# LED_Array_Large.net
KiCad netlist of a schematic drawn in Altium Designer
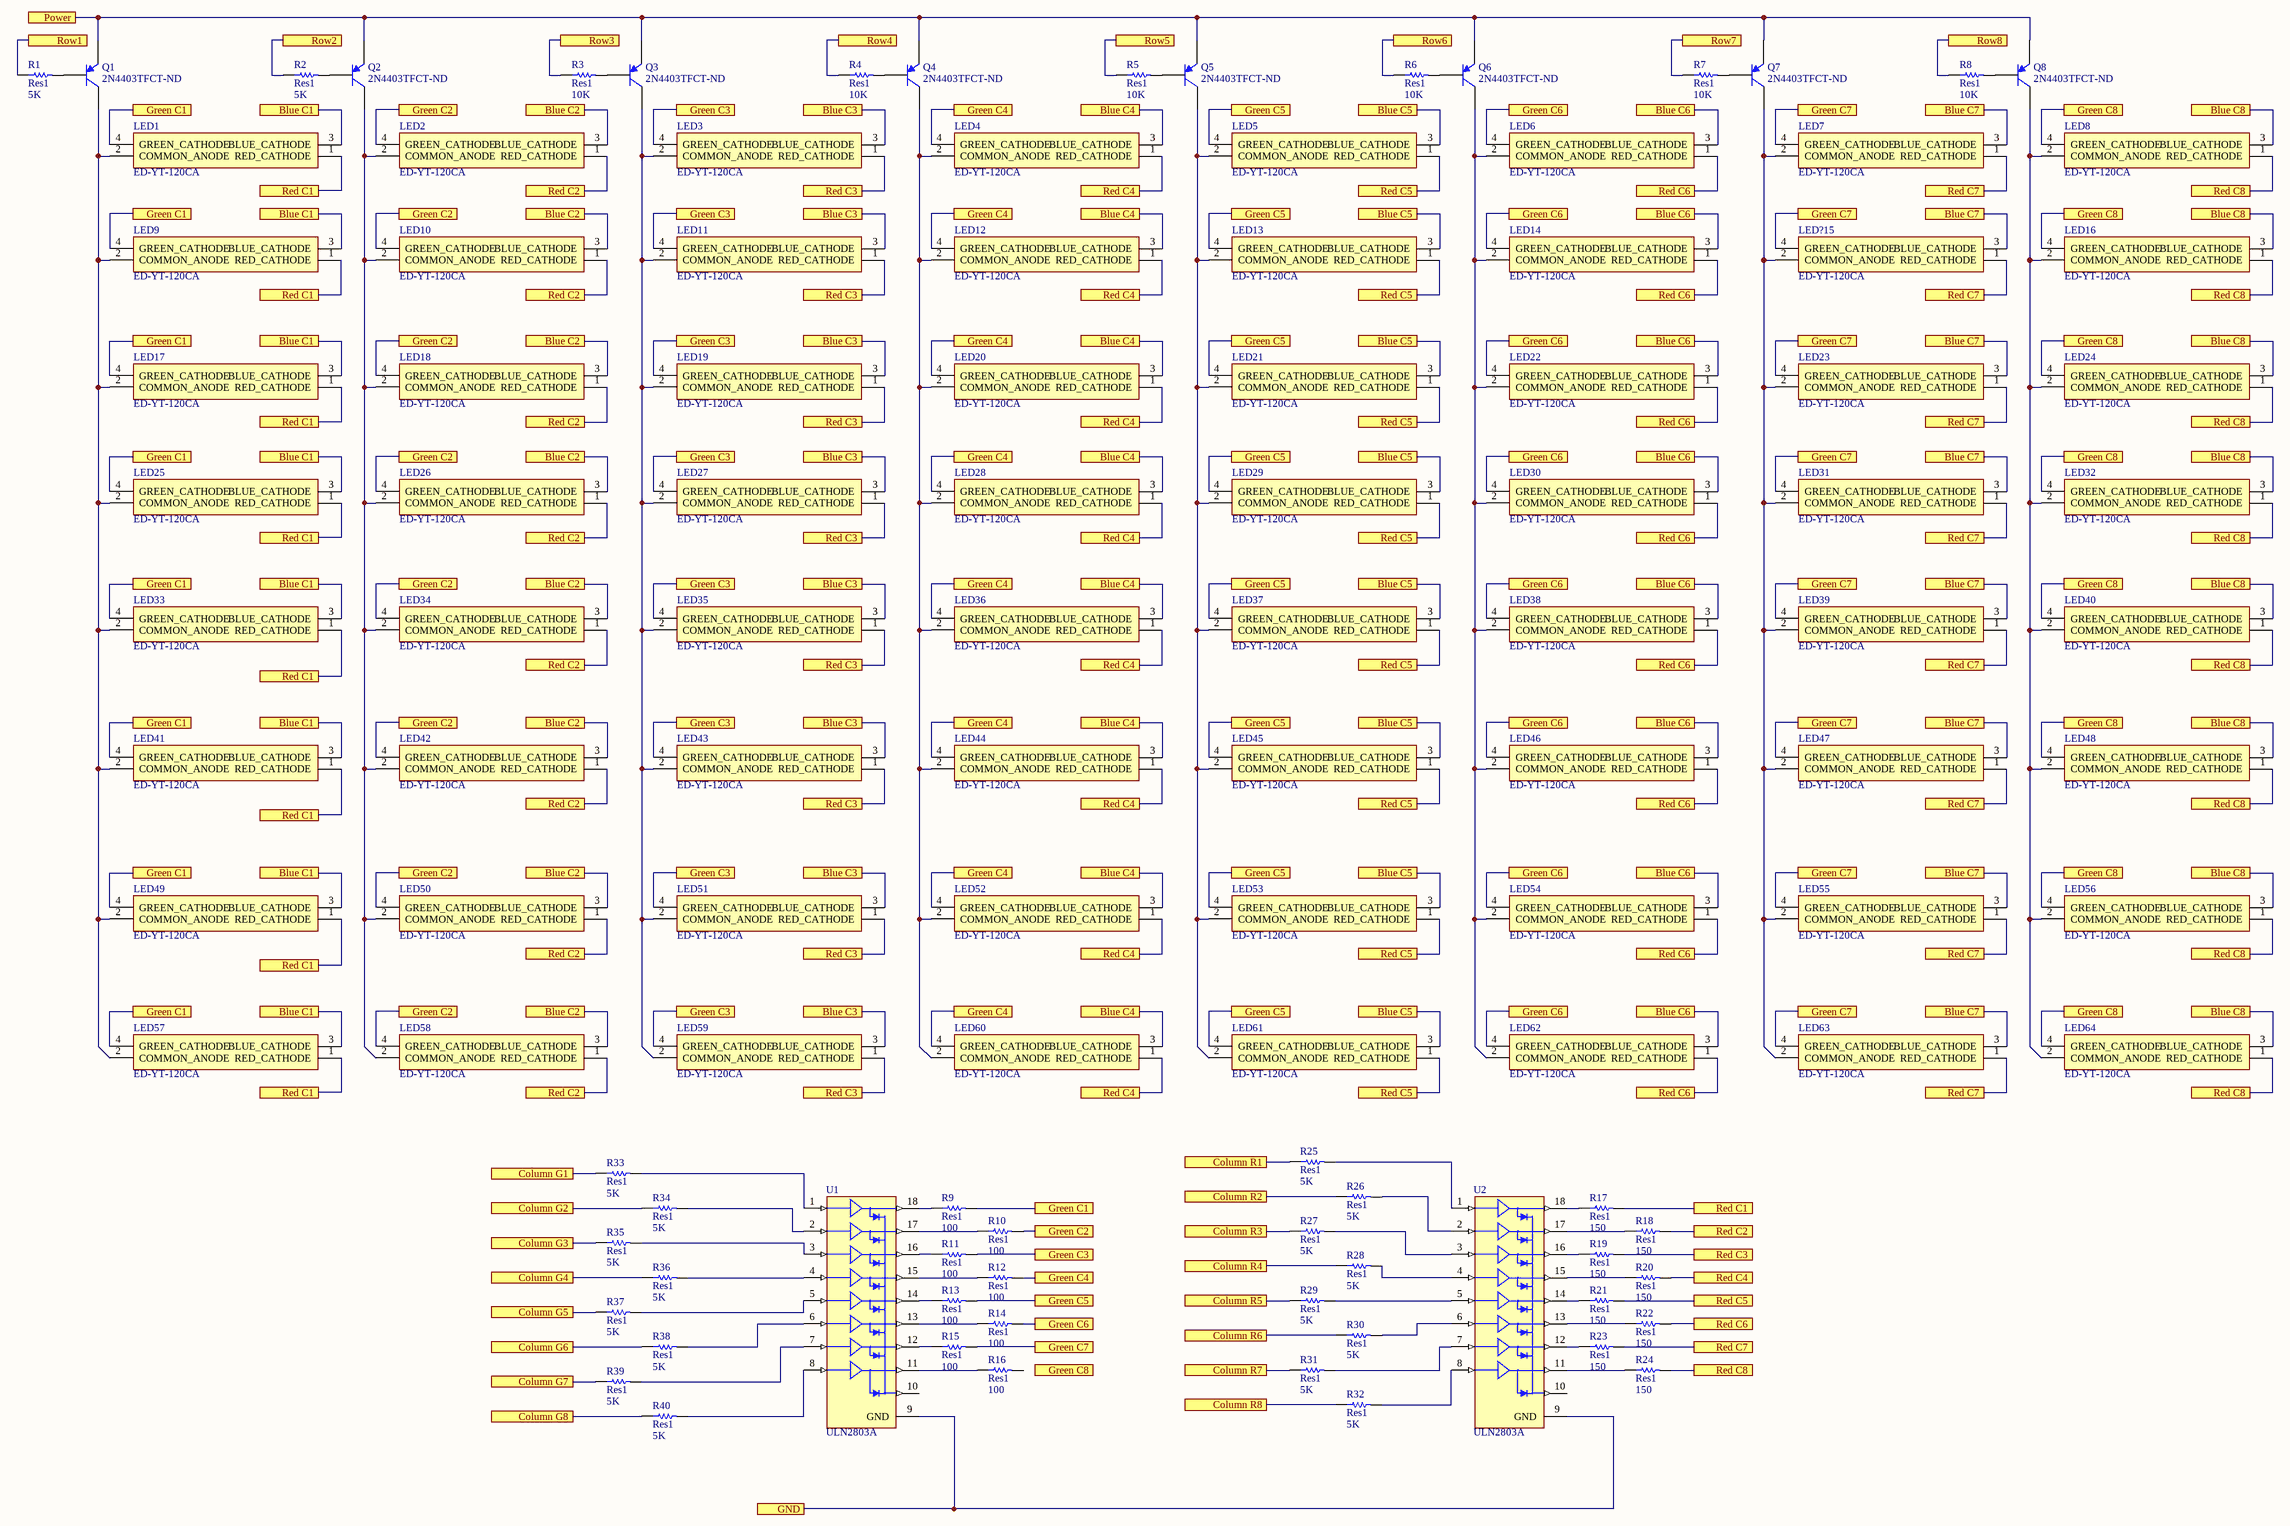
[diagram p0: LED_Array_Large.SchDoc]

(export (version "E")
  (design (tool "Eeschema 10.0.6"))
  (components
    (comp (ref "LED1")
      (value "ED-YT-120CA")
      (footprint "SamacSys:L-154A4SUREQBFZGEC")
      (description "LED")
      (fields
        (field (name "MANUFACTURER_PART_NUMBER") "WP154A4SEJ3VBDZGW/CA")
        (field (name "MOUSER PART NUMBER") "604-WP154A43VBDZGWCA")
      )
      (libsource (lib "SamacSys") (part "WP154A4SEJ3VBDZGW_CA"))
    )
    (comp (ref "LED2")
      (value "ED-YT-120CA")
      (footprint "SamacSys:L-154A4SUREQBFZGEC")
      (description "LED")
      (fields
        (field (name "MANUFACTURER_PART_NUMBER") "WP154A4SEJ3VBDZGW/CA")
        (field (name "MOUSER PART NUMBER") "604-WP154A43VBDZGWCA")
      )
      (libsource (lib "*") (part "WP154A4SEJ3VBDZGW_CA"))
    )
    (comp (ref "LED3")
      (value "ED-YT-120CA")
      (footprint "SamacSys:L-154A4SUREQBFZGEC")
      (description "LED")
      (fields
        (field (name "MANUFACTURER_PART_NUMBER") "WP154A4SEJ3VBDZGW/CA")
        (field (name "MOUSER PART NUMBER") "604-WP154A43VBDZGWCA")
      )
      (libsource (lib "SamacSys") (part "WP154A4SEJ3VBDZGW_CA"))
    )
    (comp (ref "LED4")
      (value "ED-YT-120CA")
      (footprint "SamacSys:L-154A4SUREQBFZGEC")
      (description "LED")
      (fields
        (field (name "MANUFACTURER_PART_NUMBER") "WP154A4SEJ3VBDZGW/CA")
        (field (name "MOUSER PART NUMBER") "604-WP154A43VBDZGWCA")
      )
      (libsource (lib "*") (part "WP154A4SEJ3VBDZGW_CA"))
    )
    (comp (ref "LED5")
      (value "ED-YT-120CA")
      (footprint "SamacSys:L-154A4SUREQBFZGEC")
      (description "LED")
      (fields
        (field (name "MANUFACTURER_PART_NUMBER") "WP154A4SEJ3VBDZGW/CA")
        (field (name "MOUSER PART NUMBER") "604-WP154A43VBDZGWCA")
      )
      (libsource (lib "SamacSys") (part "WP154A4SEJ3VBDZGW_CA"))
    )
    (comp (ref "LED6")
      (value "ED-YT-120CA")
      (footprint "SamacSys:L-154A4SUREQBFZGEC")
      (description "LED")
      (fields
        (field (name "MANUFACTURER_PART_NUMBER") "WP154A4SEJ3VBDZGW/CA")
        (field (name "MOUSER PART NUMBER") "604-WP154A43VBDZGWCA")
      )
      (libsource (lib "*") (part "WP154A4SEJ3VBDZGW_CA"))
    )
    (comp (ref "LED7")
      (value "ED-YT-120CA")
      (footprint "SamacSys:L-154A4SUREQBFZGEC")
      (description "LED")
      (fields
        (field (name "MANUFACTURER_PART_NUMBER") "WP154A4SEJ3VBDZGW/CA")
        (field (name "MOUSER PART NUMBER") "604-WP154A43VBDZGWCA")
      )
      (libsource (lib "SamacSys") (part "WP154A4SEJ3VBDZGW_CA"))
    )
    (comp (ref "LED8")
      (value "ED-YT-120CA")
      (footprint "SamacSys:L-154A4SUREQBFZGEC")
      (description "LED")
      (fields
        (field (name "MANUFACTURER_PART_NUMBER") "WP154A4SEJ3VBDZGW/CA")
        (field (name "MOUSER PART NUMBER") "604-WP154A43VBDZGWCA")
      )
      (libsource (lib "*") (part "WP154A4SEJ3VBDZGW_CA"))
    )
    (comp (ref "LED9")
      (value "ED-YT-120CA")
      (footprint "SamacSys:L-154A4SUREQBFZGEC")
      (description "LED")
      (fields
        (field (name "MANUFACTURER_PART_NUMBER") "WP154A4SEJ3VBDZGW/CA")
        (field (name "MOUSER PART NUMBER") "604-WP154A43VBDZGWCA")
      )
      (libsource (lib "SamacSys") (part "WP154A4SEJ3VBDZGW_CA"))
    )
    (comp (ref "LED10")
      (value "ED-YT-120CA")
      (footprint "SamacSys:L-154A4SUREQBFZGEC")
      (description "LED")
      (fields
        (field (name "MANUFACTURER_PART_NUMBER") "WP154A4SEJ3VBDZGW/CA")
        (field (name "MOUSER PART NUMBER") "604-WP154A43VBDZGWCA")
      )
      (libsource (lib "*") (part "WP154A4SEJ3VBDZGW_CA"))
    )
    (comp (ref "LED11")
      (value "ED-YT-120CA")
      (footprint "SamacSys:L-154A4SUREQBFZGEC")
      (description "LED")
      (fields
        (field (name "MANUFACTURER_PART_NUMBER") "WP154A4SEJ3VBDZGW/CA")
        (field (name "MOUSER PART NUMBER") "604-WP154A43VBDZGWCA")
      )
      (libsource (lib "SamacSys") (part "WP154A4SEJ3VBDZGW_CA"))
    )
    (comp (ref "LED12")
      (value "ED-YT-120CA")
      (footprint "SamacSys:L-154A4SUREQBFZGEC")
      (description "LED")
      (fields
        (field (name "MANUFACTURER_PART_NUMBER") "WP154A4SEJ3VBDZGW/CA")
        (field (name "MOUSER PART NUMBER") "604-WP154A43VBDZGWCA")
      )
      (libsource (lib "*") (part "WP154A4SEJ3VBDZGW_CA"))
    )
    (comp (ref "LED13")
      (value "ED-YT-120CA")
      (footprint "SamacSys:L-154A4SUREQBFZGEC")
      (description "LED")
      (fields
        (field (name "MANUFACTURER_PART_NUMBER") "WP154A4SEJ3VBDZGW/CA")
        (field (name "MOUSER PART NUMBER") "604-WP154A43VBDZGWCA")
      )
      (libsource (lib "SamacSys") (part "WP154A4SEJ3VBDZGW_CA"))
    )
    (comp (ref "LED14")
      (value "ED-YT-120CA")
      (footprint "SamacSys:L-154A4SUREQBFZGEC")
      (description "LED")
      (fields
        (field (name "MANUFACTURER_PART_NUMBER") "WP154A4SEJ3VBDZGW/CA")
        (field (name "MOUSER PART NUMBER") "604-WP154A43VBDZGWCA")
      )
      (libsource (lib "*") (part "WP154A4SEJ3VBDZGW_CA"))
    )
    (comp (ref "LED16")
      (value "ED-YT-120CA")
      (footprint "SamacSys:L-154A4SUREQBFZGEC")
      (description "LED")
      (fields
        (field (name "MANUFACTURER_PART_NUMBER") "WP154A4SEJ3VBDZGW/CA")
        (field (name "MOUSER PART NUMBER") "604-WP154A43VBDZGWCA")
      )
      (libsource (lib "*") (part "WP154A4SEJ3VBDZGW_CA"))
    )
    (comp (ref "LED17")
      (value "ED-YT-120CA")
      (footprint "SamacSys:L-154A4SUREQBFZGEC")
      (description "LED")
      (fields
        (field (name "MANUFACTURER_PART_NUMBER") "WP154A4SEJ3VBDZGW/CA")
        (field (name "MOUSER PART NUMBER") "604-WP154A43VBDZGWCA")
      )
      (libsource (lib "SamacSys") (part "WP154A4SEJ3VBDZGW_CA"))
    )
    (comp (ref "LED18")
      (value "ED-YT-120CA")
      (footprint "SamacSys:L-154A4SUREQBFZGEC")
      (description "LED")
      (fields
        (field (name "MANUFACTURER_PART_NUMBER") "WP154A4SEJ3VBDZGW/CA")
        (field (name "MOUSER PART NUMBER") "604-WP154A43VBDZGWCA")
      )
      (libsource (lib "*") (part "WP154A4SEJ3VBDZGW_CA"))
    )
    (comp (ref "LED19")
      (value "ED-YT-120CA")
      (footprint "SamacSys:L-154A4SUREQBFZGEC")
      (description "LED")
      (fields
        (field (name "MANUFACTURER_PART_NUMBER") "WP154A4SEJ3VBDZGW/CA")
        (field (name "MOUSER PART NUMBER") "604-WP154A43VBDZGWCA")
      )
      (libsource (lib "SamacSys") (part "WP154A4SEJ3VBDZGW_CA"))
    )
    (comp (ref "LED20")
      (value "ED-YT-120CA")
      (footprint "SamacSys:L-154A4SUREQBFZGEC")
      (description "LED")
      (fields
        (field (name "MANUFACTURER_PART_NUMBER") "WP154A4SEJ3VBDZGW/CA")
        (field (name "MOUSER PART NUMBER") "604-WP154A43VBDZGWCA")
      )
      (libsource (lib "*") (part "WP154A4SEJ3VBDZGW_CA"))
    )
    (comp (ref "LED21")
      (value "ED-YT-120CA")
      (footprint "SamacSys:L-154A4SUREQBFZGEC")
      (description "LED")
      (fields
        (field (name "MANUFACTURER_PART_NUMBER") "WP154A4SEJ3VBDZGW/CA")
        (field (name "MOUSER PART NUMBER") "604-WP154A43VBDZGWCA")
      )
      (libsource (lib "SamacSys") (part "WP154A4SEJ3VBDZGW_CA"))
    )
    (comp (ref "LED22")
      (value "ED-YT-120CA")
      (footprint "SamacSys:L-154A4SUREQBFZGEC")
      (description "LED")
      (fields
        (field (name "MANUFACTURER_PART_NUMBER") "WP154A4SEJ3VBDZGW/CA")
        (field (name "MOUSER PART NUMBER") "604-WP154A43VBDZGWCA")
      )
      (libsource (lib "*") (part "WP154A4SEJ3VBDZGW_CA"))
    )
    (comp (ref "LED23")
      (value "ED-YT-120CA")
      (footprint "SamacSys:L-154A4SUREQBFZGEC")
      (description "LED")
      (fields
        (field (name "MANUFACTURER_PART_NUMBER") "WP154A4SEJ3VBDZGW/CA")
        (field (name "MOUSER PART NUMBER") "604-WP154A43VBDZGWCA")
      )
      (libsource (lib "SamacSys") (part "WP154A4SEJ3VBDZGW_CA"))
    )
    (comp (ref "LED24")
      (value "ED-YT-120CA")
      (footprint "SamacSys:L-154A4SUREQBFZGEC")
      (description "LED")
      (fields
        (field (name "MANUFACTURER_PART_NUMBER") "WP154A4SEJ3VBDZGW/CA")
        (field (name "MOUSER PART NUMBER") "604-WP154A43VBDZGWCA")
      )
      (libsource (lib "*") (part "WP154A4SEJ3VBDZGW_CA"))
    )
    (comp (ref "LED25")
      (value "ED-YT-120CA")
      (footprint "SamacSys:L-154A4SUREQBFZGEC")
      (description "LED")
      (fields
        (field (name "MANUFACTURER_PART_NUMBER") "WP154A4SEJ3VBDZGW/CA")
        (field (name "MOUSER PART NUMBER") "604-WP154A43VBDZGWCA")
      )
      (libsource (lib "SamacSys") (part "WP154A4SEJ3VBDZGW_CA"))
    )
    (comp (ref "LED26")
      (value "ED-YT-120CA")
      (footprint "SamacSys:L-154A4SUREQBFZGEC")
      (description "LED")
      (fields
        (field (name "MANUFACTURER_PART_NUMBER") "WP154A4SEJ3VBDZGW/CA")
        (field (name "MOUSER PART NUMBER") "604-WP154A43VBDZGWCA")
      )
      (libsource (lib "*") (part "WP154A4SEJ3VBDZGW_CA"))
    )
    (comp (ref "LED27")
      (value "ED-YT-120CA")
      (footprint "SamacSys:L-154A4SUREQBFZGEC")
      (description "LED")
      (fields
        (field (name "MANUFACTURER_PART_NUMBER") "WP154A4SEJ3VBDZGW/CA")
        (field (name "MOUSER PART NUMBER") "604-WP154A43VBDZGWCA")
      )
      (libsource (lib "SamacSys") (part "WP154A4SEJ3VBDZGW_CA"))
    )
    (comp (ref "LED28")
      (value "ED-YT-120CA")
      (footprint "SamacSys:L-154A4SUREQBFZGEC")
      (description "LED")
      (fields
        (field (name "MANUFACTURER_PART_NUMBER") "WP154A4SEJ3VBDZGW/CA")
        (field (name "MOUSER PART NUMBER") "604-WP154A43VBDZGWCA")
      )
      (libsource (lib "*") (part "WP154A4SEJ3VBDZGW_CA"))
    )
    (comp (ref "LED29")
      (value "ED-YT-120CA")
      (footprint "SamacSys:L-154A4SUREQBFZGEC")
      (description "LED")
      (fields
        (field (name "MANUFACTURER_PART_NUMBER") "WP154A4SEJ3VBDZGW/CA")
        (field (name "MOUSER PART NUMBER") "604-WP154A43VBDZGWCA")
      )
      (libsource (lib "SamacSys") (part "WP154A4SEJ3VBDZGW_CA"))
    )
    (comp (ref "LED30")
      (value "ED-YT-120CA")
      (footprint "SamacSys:L-154A4SUREQBFZGEC")
      (description "LED")
      (fields
        (field (name "MANUFACTURER_PART_NUMBER") "WP154A4SEJ3VBDZGW/CA")
        (field (name "MOUSER PART NUMBER") "604-WP154A43VBDZGWCA")
      )
      (libsource (lib "*") (part "WP154A4SEJ3VBDZGW_CA"))
    )
    (comp (ref "LED31")
      (value "ED-YT-120CA")
      (footprint "SamacSys:L-154A4SUREQBFZGEC")
      (description "LED")
      (fields
        (field (name "MANUFACTURER_PART_NUMBER") "WP154A4SEJ3VBDZGW/CA")
        (field (name "MOUSER PART NUMBER") "604-WP154A43VBDZGWCA")
      )
      (libsource (lib "SamacSys") (part "WP154A4SEJ3VBDZGW_CA"))
    )
    (comp (ref "LED32")
      (value "ED-YT-120CA")
      (footprint "SamacSys:L-154A4SUREQBFZGEC")
      (description "LED")
      (fields
        (field (name "MANUFACTURER_PART_NUMBER") "WP154A4SEJ3VBDZGW/CA")
        (field (name "MOUSER PART NUMBER") "604-WP154A43VBDZGWCA")
      )
      (libsource (lib "*") (part "WP154A4SEJ3VBDZGW_CA"))
    )
    (comp (ref "LED33")
      (value "ED-YT-120CA")
      (footprint "SamacSys:L-154A4SUREQBFZGEC")
      (description "LED")
      (fields
        (field (name "MANUFACTURER_PART_NUMBER") "WP154A4SEJ3VBDZGW/CA")
        (field (name "MOUSER PART NUMBER") "604-WP154A43VBDZGWCA")
      )
      (libsource (lib "SamacSys") (part "WP154A4SEJ3VBDZGW_CA"))
    )
    (comp (ref "LED34")
      (value "ED-YT-120CA")
      (footprint "SamacSys:L-154A4SUREQBFZGEC")
      (description "LED")
      (fields
        (field (name "MANUFACTURER_PART_NUMBER") "WP154A4SEJ3VBDZGW/CA")
        (field (name "MOUSER PART NUMBER") "604-WP154A43VBDZGWCA")
      )
      (libsource (lib "*") (part "WP154A4SEJ3VBDZGW_CA"))
    )
    (comp (ref "LED35")
      (value "ED-YT-120CA")
      (footprint "SamacSys:L-154A4SUREQBFZGEC")
      (description "LED")
      (fields
        (field (name "MANUFACTURER_PART_NUMBER") "WP154A4SEJ3VBDZGW/CA")
        (field (name "MOUSER PART NUMBER") "604-WP154A43VBDZGWCA")
      )
      (libsource (lib "SamacSys") (part "WP154A4SEJ3VBDZGW_CA"))
    )
    (comp (ref "LED36")
      (value "ED-YT-120CA")
      (footprint "SamacSys:L-154A4SUREQBFZGEC")
      (description "LED")
      (fields
        (field (name "MANUFACTURER_PART_NUMBER") "WP154A4SEJ3VBDZGW/CA")
        (field (name "MOUSER PART NUMBER") "604-WP154A43VBDZGWCA")
      )
      (libsource (lib "*") (part "WP154A4SEJ3VBDZGW_CA"))
    )
    (comp (ref "LED37")
      (value "ED-YT-120CA")
      (footprint "SamacSys:L-154A4SUREQBFZGEC")
      (description "LED")
      (fields
        (field (name "MANUFACTURER_PART_NUMBER") "WP154A4SEJ3VBDZGW/CA")
        (field (name "MOUSER PART NUMBER") "604-WP154A43VBDZGWCA")
      )
      (libsource (lib "SamacSys") (part "WP154A4SEJ3VBDZGW_CA"))
    )
    (comp (ref "LED38")
      (value "ED-YT-120CA")
      (footprint "SamacSys:L-154A4SUREQBFZGEC")
      (description "LED")
      (fields
        (field (name "MANUFACTURER_PART_NUMBER") "WP154A4SEJ3VBDZGW/CA")
        (field (name "MOUSER PART NUMBER") "604-WP154A43VBDZGWCA")
      )
      (libsource (lib "*") (part "WP154A4SEJ3VBDZGW_CA"))
    )
    (comp (ref "LED39")
      (value "ED-YT-120CA")
      (footprint "SamacSys:L-154A4SUREQBFZGEC")
      (description "LED")
      (fields
        (field (name "MANUFACTURER_PART_NUMBER") "WP154A4SEJ3VBDZGW/CA")
        (field (name "MOUSER PART NUMBER") "604-WP154A43VBDZGWCA")
      )
      (libsource (lib "SamacSys") (part "WP154A4SEJ3VBDZGW_CA"))
    )
    (comp (ref "LED40")
      (value "ED-YT-120CA")
      (footprint "SamacSys:L-154A4SUREQBFZGEC")
      (description "LED")
      (fields
        (field (name "MANUFACTURER_PART_NUMBER") "WP154A4SEJ3VBDZGW/CA")
        (field (name "MOUSER PART NUMBER") "604-WP154A43VBDZGWCA")
      )
      (libsource (lib "*") (part "WP154A4SEJ3VBDZGW_CA"))
    )
    (comp (ref "LED41")
      (value "ED-YT-120CA")
      (footprint "SamacSys:L-154A4SUREQBFZGEC")
      (description "LED")
      (fields
        (field (name "MANUFACTURER_PART_NUMBER") "WP154A4SEJ3VBDZGW/CA")
        (field (name "MOUSER PART NUMBER") "604-WP154A43VBDZGWCA")
      )
      (libsource (lib "SamacSys") (part "WP154A4SEJ3VBDZGW_CA"))
    )
    (comp (ref "LED42")
      (value "ED-YT-120CA")
      (footprint "SamacSys:L-154A4SUREQBFZGEC")
      (description "LED")
      (fields
        (field (name "MANUFACTURER_PART_NUMBER") "WP154A4SEJ3VBDZGW/CA")
        (field (name "MOUSER PART NUMBER") "604-WP154A43VBDZGWCA")
      )
      (libsource (lib "*") (part "WP154A4SEJ3VBDZGW_CA"))
    )
    (comp (ref "LED43")
      (value "ED-YT-120CA")
      (footprint "SamacSys:L-154A4SUREQBFZGEC")
      (description "LED")
      (fields
        (field (name "MANUFACTURER_PART_NUMBER") "WP154A4SEJ3VBDZGW/CA")
        (field (name "MOUSER PART NUMBER") "604-WP154A43VBDZGWCA")
      )
      (libsource (lib "SamacSys") (part "WP154A4SEJ3VBDZGW_CA"))
    )
    (comp (ref "LED44")
      (value "ED-YT-120CA")
      (footprint "SamacSys:L-154A4SUREQBFZGEC")
      (description "LED")
      (fields
        (field (name "MANUFACTURER_PART_NUMBER") "WP154A4SEJ3VBDZGW/CA")
        (field (name "MOUSER PART NUMBER") "604-WP154A43VBDZGWCA")
      )
      (libsource (lib "*") (part "WP154A4SEJ3VBDZGW_CA"))
    )
    (comp (ref "LED45")
      (value "ED-YT-120CA")
      (footprint "SamacSys:L-154A4SUREQBFZGEC")
      (description "LED")
      (fields
        (field (name "MANUFACTURER_PART_NUMBER") "WP154A4SEJ3VBDZGW/CA")
        (field (name "MOUSER PART NUMBER") "604-WP154A43VBDZGWCA")
      )
      (libsource (lib "SamacSys") (part "WP154A4SEJ3VBDZGW_CA"))
    )
    (comp (ref "LED46")
      (value "ED-YT-120CA")
      (footprint "SamacSys:L-154A4SUREQBFZGEC")
      (description "LED")
      (fields
        (field (name "MANUFACTURER_PART_NUMBER") "WP154A4SEJ3VBDZGW/CA")
        (field (name "MOUSER PART NUMBER") "604-WP154A43VBDZGWCA")
      )
      (libsource (lib "*") (part "WP154A4SEJ3VBDZGW_CA"))
    )
    (comp (ref "LED47")
      (value "ED-YT-120CA")
      (footprint "SamacSys:L-154A4SUREQBFZGEC")
      (description "LED")
      (fields
        (field (name "MANUFACTURER_PART_NUMBER") "WP154A4SEJ3VBDZGW/CA")
        (field (name "MOUSER PART NUMBER") "604-WP154A43VBDZGWCA")
      )
      (libsource (lib "SamacSys") (part "WP154A4SEJ3VBDZGW_CA"))
    )
    (comp (ref "LED48")
      (value "ED-YT-120CA")
      (footprint "SamacSys:L-154A4SUREQBFZGEC")
      (description "LED")
      (fields
        (field (name "MANUFACTURER_PART_NUMBER") "WP154A4SEJ3VBDZGW/CA")
        (field (name "MOUSER PART NUMBER") "604-WP154A43VBDZGWCA")
      )
      (libsource (lib "*") (part "WP154A4SEJ3VBDZGW_CA"))
    )
    (comp (ref "LED49")
      (value "ED-YT-120CA")
      (footprint "SamacSys:L-154A4SUREQBFZGEC")
      (description "LED")
      (fields
        (field (name "MANUFACTURER_PART_NUMBER") "WP154A4SEJ3VBDZGW/CA")
        (field (name "MOUSER PART NUMBER") "604-WP154A43VBDZGWCA")
      )
      (libsource (lib "SamacSys") (part "WP154A4SEJ3VBDZGW_CA"))
    )
    (comp (ref "LED50")
      (value "ED-YT-120CA")
      (footprint "SamacSys:L-154A4SUREQBFZGEC")
      (description "LED")
      (fields
        (field (name "MANUFACTURER_PART_NUMBER") "WP154A4SEJ3VBDZGW/CA")
        (field (name "MOUSER PART NUMBER") "604-WP154A43VBDZGWCA")
      )
      (libsource (lib "*") (part "WP154A4SEJ3VBDZGW_CA"))
    )
    (comp (ref "LED51")
      (value "ED-YT-120CA")
      (footprint "SamacSys:L-154A4SUREQBFZGEC")
      (description "LED")
      (fields
        (field (name "MANUFACTURER_PART_NUMBER") "WP154A4SEJ3VBDZGW/CA")
        (field (name "MOUSER PART NUMBER") "604-WP154A43VBDZGWCA")
      )
      (libsource (lib "SamacSys") (part "WP154A4SEJ3VBDZGW_CA"))
    )
    (comp (ref "LED52")
      (value "ED-YT-120CA")
      (footprint "SamacSys:L-154A4SUREQBFZGEC")
      (description "LED")
      (fields
        (field (name "MANUFACTURER_PART_NUMBER") "WP154A4SEJ3VBDZGW/CA")
        (field (name "MOUSER PART NUMBER") "604-WP154A43VBDZGWCA")
      )
      (libsource (lib "*") (part "WP154A4SEJ3VBDZGW_CA"))
    )
    (comp (ref "LED53")
      (value "ED-YT-120CA")
      (footprint "SamacSys:L-154A4SUREQBFZGEC")
      (description "LED")
      (fields
        (field (name "MANUFACTURER_PART_NUMBER") "WP154A4SEJ3VBDZGW/CA")
        (field (name "MOUSER PART NUMBER") "604-WP154A43VBDZGWCA")
      )
      (libsource (lib "SamacSys") (part "WP154A4SEJ3VBDZGW_CA"))
    )
    (comp (ref "LED54")
      (value "ED-YT-120CA")
      (footprint "SamacSys:L-154A4SUREQBFZGEC")
      (description "LED")
      (fields
        (field (name "MANUFACTURER_PART_NUMBER") "WP154A4SEJ3VBDZGW/CA")
        (field (name "MOUSER PART NUMBER") "604-WP154A43VBDZGWCA")
      )
      (libsource (lib "*") (part "WP154A4SEJ3VBDZGW_CA"))
    )
    (comp (ref "LED55")
      (value "ED-YT-120CA")
      (footprint "SamacSys:L-154A4SUREQBFZGEC")
      (description "LED")
      (fields
        (field (name "MANUFACTURER_PART_NUMBER") "WP154A4SEJ3VBDZGW/CA")
        (field (name "MOUSER PART NUMBER") "604-WP154A43VBDZGWCA")
      )
      (libsource (lib "SamacSys") (part "WP154A4SEJ3VBDZGW_CA"))
    )
    (comp (ref "LED56")
      (value "ED-YT-120CA")
      (footprint "SamacSys:L-154A4SUREQBFZGEC")
      (description "LED")
      (fields
        (field (name "MANUFACTURER_PART_NUMBER") "WP154A4SEJ3VBDZGW/CA")
        (field (name "MOUSER PART NUMBER") "604-WP154A43VBDZGWCA")
      )
      (libsource (lib "*") (part "WP154A4SEJ3VBDZGW_CA"))
    )
    (comp (ref "LED57")
      (value "ED-YT-120CA")
      (footprint "SamacSys:L-154A4SUREQBFZGEC")
      (description "LED")
      (fields
        (field (name "MANUFACTURER_PART_NUMBER") "WP154A4SEJ3VBDZGW/CA")
        (field (name "MOUSER PART NUMBER") "604-WP154A43VBDZGWCA")
      )
      (libsource (lib "SamacSys") (part "WP154A4SEJ3VBDZGW_CA"))
    )
    (comp (ref "LED58")
      (value "ED-YT-120CA")
      (footprint "SamacSys:L-154A4SUREQBFZGEC")
      (description "LED")
      (fields
        (field (name "MANUFACTURER_PART_NUMBER") "WP154A4SEJ3VBDZGW/CA")
        (field (name "MOUSER PART NUMBER") "604-WP154A43VBDZGWCA")
      )
      (libsource (lib "*") (part "WP154A4SEJ3VBDZGW_CA"))
    )
    (comp (ref "LED59")
      (value "ED-YT-120CA")
      (footprint "SamacSys:L-154A4SUREQBFZGEC")
      (description "LED")
      (fields
        (field (name "MANUFACTURER_PART_NUMBER") "WP154A4SEJ3VBDZGW/CA")
        (field (name "MOUSER PART NUMBER") "604-WP154A43VBDZGWCA")
      )
      (libsource (lib "SamacSys") (part "WP154A4SEJ3VBDZGW_CA"))
    )
    (comp (ref "LED60")
      (value "ED-YT-120CA")
      (footprint "SamacSys:L-154A4SUREQBFZGEC")
      (description "LED")
      (fields
        (field (name "MANUFACTURER_PART_NUMBER") "WP154A4SEJ3VBDZGW/CA")
        (field (name "MOUSER PART NUMBER") "604-WP154A43VBDZGWCA")
      )
      (libsource (lib "*") (part "WP154A4SEJ3VBDZGW_CA"))
    )
    (comp (ref "LED61")
      (value "ED-YT-120CA")
      (footprint "SamacSys:L-154A4SUREQBFZGEC")
      (description "LED")
      (fields
        (field (name "MANUFACTURER_PART_NUMBER") "WP154A4SEJ3VBDZGW/CA")
        (field (name "MOUSER PART NUMBER") "604-WP154A43VBDZGWCA")
      )
      (libsource (lib "SamacSys") (part "WP154A4SEJ3VBDZGW_CA"))
    )
    (comp (ref "LED62")
      (value "ED-YT-120CA")
      (footprint "SamacSys:L-154A4SUREQBFZGEC")
      (description "LED")
      (fields
        (field (name "MANUFACTURER_PART_NUMBER") "WP154A4SEJ3VBDZGW/CA")
        (field (name "MOUSER PART NUMBER") "604-WP154A43VBDZGWCA")
      )
      (libsource (lib "*") (part "WP154A4SEJ3VBDZGW_CA"))
    )
    (comp (ref "LED63")
      (value "ED-YT-120CA")
      (footprint "SamacSys:L-154A4SUREQBFZGEC")
      (description "LED")
      (fields
        (field (name "MANUFACTURER_PART_NUMBER") "WP154A4SEJ3VBDZGW/CA")
        (field (name "MOUSER PART NUMBER") "604-WP154A43VBDZGWCA")
      )
      (libsource (lib "SamacSys") (part "WP154A4SEJ3VBDZGW_CA"))
    )
    (comp (ref "LED64")
      (value "ED-YT-120CA")
      (footprint "SamacSys:L-154A4SUREQBFZGEC")
      (description "LED")
      (fields
        (field (name "MANUFACTURER_PART_NUMBER") "WP154A4SEJ3VBDZGW/CA")
        (field (name "MOUSER PART NUMBER") "604-WP154A43VBDZGWCA")
      )
      (libsource (lib "*") (part "WP154A4SEJ3VBDZGW_CA"))
    )
    (comp (ref "LED?15")
      (value "ED-YT-120CA")
      (footprint "SamacSys:L-154A4SUREQBFZGEC")
      (description "LED")
      (fields
        (field (name "MANUFACTURER_PART_NUMBER") "WP154A4SEJ3VBDZGW/CA")
        (field (name "MOUSER PART NUMBER") "604-WP154A43VBDZGWCA")
      )
      (libsource (lib "SamacSys") (part "WP154A4SEJ3VBDZGW_CA"))
    )
    (comp (ref "Q1")
      (value "2N4403TFCT-ND")
      (footprint "TO-92A")
      (description "PNP General Purpose Amplifier")
      (fields (field (name "PUBLISHER") "Altium Limited"))
      (libsource (lib "Miscellaneous Devices") (part "2N3906"))
    )
    (comp (ref "Q2")
      (value "2N4403TFCT-ND")
      (footprint "TO-92A")
      (description "PNP General Purpose Amplifier")
      (fields (field (name "PUBLISHER") "Altium Limited"))
      (libsource (lib "Miscellaneous Devices") (part "2N3906"))
    )
    (comp (ref "Q3")
      (value "2N4403TFCT-ND")
      (footprint "TO-92A")
      (description "PNP General Purpose Amplifier")
      (fields (field (name "PUBLISHER") "Altium Limited"))
      (libsource (lib "Miscellaneous Devices") (part "2N3906"))
    )
    (comp (ref "Q4")
      (value "2N4403TFCT-ND")
      (footprint "TO-92A")
      (description "PNP General Purpose Amplifier")
      (fields (field (name "PUBLISHER") "Altium Limited"))
      (libsource (lib "Miscellaneous Devices") (part "2N3906"))
    )
    (comp (ref "Q5")
      (value "2N4403TFCT-ND")
      (footprint "TO-92A")
      (description "PNP General Purpose Amplifier")
      (fields (field (name "PUBLISHER") "Altium Limited"))
      (libsource (lib "Miscellaneous Devices") (part "2N3906"))
    )
    (comp (ref "Q6")
      (value "2N4403TFCT-ND")
      (footprint "TO-92A")
      (description "PNP General Purpose Amplifier")
      (fields (field (name "PUBLISHER") "Altium Limited"))
      (libsource (lib "Miscellaneous Devices") (part "2N3906"))
    )
    (comp (ref "Q7")
      (value "2N4403TFCT-ND")
      (footprint "TO-92A")
      (description "PNP General Purpose Amplifier")
      (fields (field (name "PUBLISHER") "Altium Limited"))
      (libsource (lib "Miscellaneous Devices") (part "2N3906"))
    )
    (comp (ref "Q8")
      (value "2N4403TFCT-ND")
      (footprint "TO-92A")
      (description "PNP General Purpose Amplifier")
      (fields (field (name "PUBLISHER") "Altium Limited"))
      (libsource (lib "Miscellaneous Devices") (part "2N3906"))
    )
    (comp (ref "R1")
      (value "Res1")
      (footprint "AXIAL-0.3")
      (description "Resistor")
      (fields (field (name "ALTIUM_VALUE") "5K") (field (name "PUBLISHER") "Altium Limited"))
      (libsource (lib "Miscellaneous Devices") (part "Res1"))
    )
    (comp (ref "R2")
      (value "Res1")
      (footprint "AXIAL-0.3")
      (description "Resistor")
      (fields (field (name "ALTIUM_VALUE") "5K") (field (name "PUBLISHER") "Altium Limited"))
      (libsource (lib "Miscellaneous Devices") (part "Res1"))
    )
    (comp (ref "R3")
      (value "Res1")
      (footprint "AXIAL-0.3")
      (description "Resistor")
      (fields (field (name "ALTIUM_VALUE") "10K") (field (name "PUBLISHER") "Altium Limited"))
      (libsource (lib "Miscellaneous Devices") (part "Res1"))
    )
    (comp (ref "R4")
      (value "Res1")
      (footprint "AXIAL-0.3")
      (description "Resistor")
      (fields (field (name "ALTIUM_VALUE") "10K") (field (name "PUBLISHER") "Altium Limited"))
      (libsource (lib "Miscellaneous Devices") (part "Res1"))
    )
    (comp (ref "R5")
      (value "Res1")
      (footprint "AXIAL-0.3")
      (description "Resistor")
      (fields (field (name "ALTIUM_VALUE") "10K") (field (name "PUBLISHER") "Altium Limited"))
      (libsource (lib "Miscellaneous Devices") (part "Res1"))
    )
    (comp (ref "R6")
      (value "Res1")
      (footprint "AXIAL-0.3")
      (description "Resistor")
      (fields (field (name "ALTIUM_VALUE") "10K") (field (name "PUBLISHER") "Altium Limited"))
      (libsource (lib "Miscellaneous Devices") (part "Res1"))
    )
    (comp (ref "R7")
      (value "Res1")
      (footprint "AXIAL-0.3")
      (description "Resistor")
      (fields (field (name "ALTIUM_VALUE") "10K") (field (name "PUBLISHER") "Altium Limited"))
      (libsource (lib "Miscellaneous Devices") (part "Res1"))
    )
    (comp (ref "R8")
      (value "Res1")
      (footprint "AXIAL-0.3")
      (description "Resistor")
      (fields (field (name "ALTIUM_VALUE") "10K") (field (name "PUBLISHER") "Altium Limited"))
      (libsource (lib "Miscellaneous Devices") (part "Res1"))
    )
    (comp (ref "R9")
      (value "Res1")
      (footprint "AXIAL-0.3")
      (description "Resistor")
      (fields (field (name "ALTIUM_VALUE") "100") (field (name "PUBLISHER") "Altium Limited"))
      (libsource (lib "Miscellaneous Devices") (part "Res1"))
    )
    (comp (ref "R10")
      (value "Res1")
      (footprint "AXIAL-0.3")
      (description "Resistor")
      (fields (field (name "ALTIUM_VALUE") "100") (field (name "PUBLISHER") "Altium Limited"))
      (libsource (lib "Miscellaneous Devices") (part "Res1"))
    )
    (comp (ref "R11")
      (value "Res1")
      (footprint "AXIAL-0.3")
      (description "Resistor")
      (fields (field (name "ALTIUM_VALUE") "100") (field (name "PUBLISHER") "Altium Limited"))
      (libsource (lib "Miscellaneous Devices") (part "Res1"))
    )
    (comp (ref "R12")
      (value "Res1")
      (footprint "AXIAL-0.3")
      (description "Resistor")
      (fields (field (name "ALTIUM_VALUE") "100") (field (name "PUBLISHER") "Altium Limited"))
      (libsource (lib "Miscellaneous Devices") (part "Res1"))
    )
    (comp (ref "R13")
      (value "Res1")
      (footprint "AXIAL-0.3")
      (description "Resistor")
      (fields (field (name "ALTIUM_VALUE") "100") (field (name "PUBLISHER") "Altium Limited"))
      (libsource (lib "Miscellaneous Devices") (part "Res1"))
    )
    (comp (ref "R14")
      (value "Res1")
      (footprint "AXIAL-0.3")
      (description "Resistor")
      (fields (field (name "ALTIUM_VALUE") "100") (field (name "PUBLISHER") "Altium Limited"))
      (libsource (lib "Miscellaneous Devices") (part "Res1"))
    )
    (comp (ref "R15")
      (value "Res1")
      (footprint "AXIAL-0.3")
      (description "Resistor")
      (fields (field (name "ALTIUM_VALUE") "100") (field (name "PUBLISHER") "Altium Limited"))
      (libsource (lib "Miscellaneous Devices") (part "Res1"))
    )
    (comp (ref "R16")
      (value "Res1")
      (footprint "AXIAL-0.3")
      (description "Resistor")
      (fields (field (name "ALTIUM_VALUE") "100") (field (name "PUBLISHER") "Altium Limited"))
      (libsource (lib "Miscellaneous Devices") (part "Res1"))
    )
    (comp (ref "R17")
      (value "Res1")
      (footprint "AXIAL-0.3")
      (description "Resistor")
      (fields (field (name "ALTIUM_VALUE") "150") (field (name "PUBLISHER") "Altium Limited"))
      (libsource (lib "Miscellaneous Devices") (part "Res1"))
    )
    (comp (ref "R18")
      (value "Res1")
      (footprint "AXIAL-0.3")
      (description "Resistor")
      (fields (field (name "ALTIUM_VALUE") "150") (field (name "PUBLISHER") "Altium Limited"))
      (libsource (lib "Miscellaneous Devices") (part "Res1"))
    )
    (comp (ref "R19")
      (value "Res1")
      (footprint "AXIAL-0.3")
      (description "Resistor")
      (fields (field (name "ALTIUM_VALUE") "150") (field (name "PUBLISHER") "Altium Limited"))
      (libsource (lib "Miscellaneous Devices") (part "Res1"))
    )
    (comp (ref "R20")
      (value "Res1")
      (footprint "AXIAL-0.3")
      (description "Resistor")
      (fields (field (name "ALTIUM_VALUE") "150") (field (name "PUBLISHER") "Altium Limited"))
      (libsource (lib "Miscellaneous Devices") (part "Res1"))
    )
    (comp (ref "R21")
      (value "Res1")
      (footprint "AXIAL-0.3")
      (description "Resistor")
      (fields (field (name "ALTIUM_VALUE") "150") (field (name "PUBLISHER") "Altium Limited"))
      (libsource (lib "Miscellaneous Devices") (part "Res1"))
    )
    (comp (ref "R22")
      (value "Res1")
      (footprint "AXIAL-0.3")
      (description "Resistor")
      (fields (field (name "ALTIUM_VALUE") "150") (field (name "PUBLISHER") "Altium Limited"))
      (libsource (lib "Miscellaneous Devices") (part "Res1"))
    )
    (comp (ref "R23")
      (value "Res1")
      (footprint "AXIAL-0.3")
      (description "Resistor")
      (fields (field (name "ALTIUM_VALUE") "150") (field (name "PUBLISHER") "Altium Limited"))
      (libsource (lib "Miscellaneous Devices") (part "Res1"))
    )
    (comp (ref "R24")
      (value "Res1")
      (footprint "AXIAL-0.3")
      (description "Resistor")
      (fields (field (name "ALTIUM_VALUE") "150") (field (name "PUBLISHER") "Altium Limited"))
      (libsource (lib "Miscellaneous Devices") (part "Res1"))
    )
    (comp (ref "R25")
      (value "Res1")
      (footprint "AXIAL-0.3")
      (description "Resistor")
      (fields (field (name "ALTIUM_VALUE") "5K") (field (name "PUBLISHER") "Altium Limited"))
      (libsource (lib "Miscellaneous Devices") (part "Res1"))
    )
    (comp (ref "R26")
      (value "Res1")
      (footprint "AXIAL-0.3")
      (description "Resistor")
      (fields (field (name "ALTIUM_VALUE") "5K") (field (name "PUBLISHER") "Altium Limited"))
      (libsource (lib "Miscellaneous Devices") (part "Res1"))
    )
    (comp (ref "R27")
      (value "Res1")
      (footprint "AXIAL-0.3")
      (description "Resistor")
      (fields (field (name "ALTIUM_VALUE") "5K") (field (name "PUBLISHER") "Altium Limited"))
      (libsource (lib "Miscellaneous Devices") (part "Res1"))
    )
    (comp (ref "R28")
      (value "Res1")
      (footprint "AXIAL-0.3")
      (description "Resistor")
      (fields (field (name "ALTIUM_VALUE") "5K") (field (name "PUBLISHER") "Altium Limited"))
      (libsource (lib "Miscellaneous Devices") (part "Res1"))
    )
    (comp (ref "R29")
      (value "Res1")
      (footprint "AXIAL-0.3")
      (description "Resistor")
      (fields (field (name "ALTIUM_VALUE") "5K") (field (name "PUBLISHER") "Altium Limited"))
      (libsource (lib "Miscellaneous Devices") (part "Res1"))
    )
    (comp (ref "R30")
      (value "Res1")
      (footprint "AXIAL-0.3")
      (description "Resistor")
      (fields (field (name "ALTIUM_VALUE") "5K") (field (name "PUBLISHER") "Altium Limited"))
      (libsource (lib "Miscellaneous Devices") (part "Res1"))
    )
    (comp (ref "R31")
      (value "Res1")
      (footprint "AXIAL-0.3")
      (description "Resistor")
      (fields (field (name "ALTIUM_VALUE") "5K") (field (name "PUBLISHER") "Altium Limited"))
      (libsource (lib "Miscellaneous Devices") (part "Res1"))
    )
    (comp (ref "R32")
      (value "Res1")
      (footprint "AXIAL-0.3")
      (description "Resistor")
      (fields (field (name "ALTIUM_VALUE") "5K") (field (name "PUBLISHER") "Altium Limited"))
      (libsource (lib "Miscellaneous Devices") (part "Res1"))
    )
    (comp (ref "R33")
      (value "Res1")
      (footprint "AXIAL-0.3")
      (description "Resistor")
      (fields (field (name "ALTIUM_VALUE") "5K") (field (name "PUBLISHER") "Altium Limited"))
      (libsource (lib "Miscellaneous Devices") (part "Res1"))
    )
    (comp (ref "R34")
      (value "Res1")
      (footprint "AXIAL-0.3")
      (description "Resistor")
      (fields (field (name "ALTIUM_VALUE") "5K") (field (name "PUBLISHER") "Altium Limited"))
      (libsource (lib "Miscellaneous Devices") (part "Res1"))
    )
    (comp (ref "R35")
      (value "Res1")
      (footprint "AXIAL-0.3")
      (description "Resistor")
      (fields (field (name "ALTIUM_VALUE") "5K") (field (name "PUBLISHER") "Altium Limited"))
      (libsource (lib "Miscellaneous Devices") (part "Res1"))
    )
    (comp (ref "R36")
      (value "Res1")
      (footprint "AXIAL-0.3")
      (description "Resistor")
      (fields (field (name "ALTIUM_VALUE") "5K") (field (name "PUBLISHER") "Altium Limited"))
      (libsource (lib "Miscellaneous Devices") (part "Res1"))
    )
    (comp (ref "R37")
      (value "Res1")
      (footprint "AXIAL-0.3")
      (description "Resistor")
      (fields (field (name "ALTIUM_VALUE") "5K") (field (name "PUBLISHER") "Altium Limited"))
      (libsource (lib "Miscellaneous Devices") (part "Res1"))
    )
    (comp (ref "R38")
      (value "Res1")
      (footprint "AXIAL-0.3")
      (description "Resistor")
      (fields (field (name "ALTIUM_VALUE") "5K") (field (name "PUBLISHER") "Altium Limited"))
      (libsource (lib "Miscellaneous Devices") (part "Res1"))
    )
    (comp (ref "R39")
      (value "Res1")
      (footprint "AXIAL-0.3")
      (description "Resistor")
      (fields (field (name "ALTIUM_VALUE") "5K") (field (name "PUBLISHER") "Altium Limited"))
      (libsource (lib "Miscellaneous Devices") (part "Res1"))
    )
    (comp (ref "R40")
      (value "Res1")
      (footprint "AXIAL-0.3")
      (description "Resistor")
      (fields (field (name "ALTIUM_VALUE") "5K") (field (name "PUBLISHER") "Altium Limited"))
      (libsource (lib "Miscellaneous Devices") (part "Res1"))
    )
    (comp (ref "U1")
      (value "ULN2803A")
      (footprint "DIP850W46P254L2324H393Q18")
      (description "Bipolar _BJT_ Transistor Array 8 NPN Darlington 50V 500mA 2.25W Through Hole 18-DIP")
      (fields (field (name "MF") "STMicroelectronics"))
      (libsource (lib "ULN2803A") (part "ULN2803A"))
    )
    (comp (ref "U2")
      (value "ULN2803A")
      (footprint "DIP850W46P254L2324H393Q18")
      (description "Bipolar _BJT_ Transistor Array 8 NPN Darlington 50V 500mA 2.25W Through Hole 18-DIP")
      (fields (field (name "MF") "STMicroelectronics"))
      (libsource (lib "ULN2803A") (part "ULN2803A"))
    )
  )
  (nets
    (net (code "1") (name "/Blue C1") (class "Default")
      (node (ref "LED1") (pin "3") (pinfunction "BLUE_CATHODE_3") (pintype "passive"))
      (node (ref "LED17") (pin "3") (pinfunction "BLUE_CATHODE_3") (pintype "passive"))
      (node (ref "LED25") (pin "3") (pinfunction "BLUE_CATHODE_3") (pintype "passive"))
      (node (ref "LED33") (pin "3") (pinfunction "BLUE_CATHODE_3") (pintype "passive"))
      (node (ref "LED41") (pin "3") (pinfunction "BLUE_CATHODE_3") (pintype "passive"))
      (node (ref "LED49") (pin "3") (pinfunction "BLUE_CATHODE_3") (pintype "passive"))
      (node (ref "LED57") (pin "3") (pinfunction "BLUE_CATHODE_3") (pintype "passive"))
      (node (ref "LED9") (pin "3") (pinfunction "BLUE_CATHODE_3") (pintype "passive"))
    )
    (net (code "2") (name "/Blue C2") (class "Default")
      (node (ref "LED10") (pin "3") (pinfunction "BLUE_CATHODE_3") (pintype "passive"))
      (node (ref "LED18") (pin "3") (pinfunction "BLUE_CATHODE_3") (pintype "passive"))
      (node (ref "LED2") (pin "3") (pinfunction "BLUE_CATHODE_3") (pintype "passive"))
      (node (ref "LED26") (pin "3") (pinfunction "BLUE_CATHODE_3") (pintype "passive"))
      (node (ref "LED34") (pin "3") (pinfunction "BLUE_CATHODE_3") (pintype "passive"))
      (node (ref "LED42") (pin "3") (pinfunction "BLUE_CATHODE_3") (pintype "passive"))
      (node (ref "LED50") (pin "3") (pinfunction "BLUE_CATHODE_3") (pintype "passive"))
      (node (ref "LED58") (pin "3") (pinfunction "BLUE_CATHODE_3") (pintype "passive"))
    )
    (net (code "3") (name "/Blue C3") (class "Default")
      (node (ref "LED11") (pin "3") (pinfunction "BLUE_CATHODE_3") (pintype "passive"))
      (node (ref "LED19") (pin "3") (pinfunction "BLUE_CATHODE_3") (pintype "passive"))
      (node (ref "LED27") (pin "3") (pinfunction "BLUE_CATHODE_3") (pintype "passive"))
      (node (ref "LED3") (pin "3") (pinfunction "BLUE_CATHODE_3") (pintype "passive"))
      (node (ref "LED35") (pin "3") (pinfunction "BLUE_CATHODE_3") (pintype "passive"))
      (node (ref "LED43") (pin "3") (pinfunction "BLUE_CATHODE_3") (pintype "passive"))
      (node (ref "LED51") (pin "3") (pinfunction "BLUE_CATHODE_3") (pintype "passive"))
      (node (ref "LED59") (pin "3") (pinfunction "BLUE_CATHODE_3") (pintype "passive"))
    )
    (net (code "4") (name "/Blue C4") (class "Default")
      (node (ref "LED12") (pin "3") (pinfunction "BLUE_CATHODE_3") (pintype "passive"))
      (node (ref "LED20") (pin "3") (pinfunction "BLUE_CATHODE_3") (pintype "passive"))
      (node (ref "LED28") (pin "3") (pinfunction "BLUE_CATHODE_3") (pintype "passive"))
      (node (ref "LED36") (pin "3") (pinfunction "BLUE_CATHODE_3") (pintype "passive"))
      (node (ref "LED4") (pin "3") (pinfunction "BLUE_CATHODE_3") (pintype "passive"))
      (node (ref "LED44") (pin "3") (pinfunction "BLUE_CATHODE_3") (pintype "passive"))
      (node (ref "LED52") (pin "3") (pinfunction "BLUE_CATHODE_3") (pintype "passive"))
      (node (ref "LED60") (pin "3") (pinfunction "BLUE_CATHODE_3") (pintype "passive"))
    )
    (net (code "5") (name "/Blue C5") (class "Default")
      (node (ref "LED13") (pin "3") (pinfunction "BLUE_CATHODE_3") (pintype "passive"))
      (node (ref "LED21") (pin "3") (pinfunction "BLUE_CATHODE_3") (pintype "passive"))
      (node (ref "LED29") (pin "3") (pinfunction "BLUE_CATHODE_3") (pintype "passive"))
      (node (ref "LED37") (pin "3") (pinfunction "BLUE_CATHODE_3") (pintype "passive"))
      (node (ref "LED45") (pin "3") (pinfunction "BLUE_CATHODE_3") (pintype "passive"))
      (node (ref "LED5") (pin "3") (pinfunction "BLUE_CATHODE_3") (pintype "passive"))
      (node (ref "LED53") (pin "3") (pinfunction "BLUE_CATHODE_3") (pintype "passive"))
      (node (ref "LED61") (pin "3") (pinfunction "BLUE_CATHODE_3") (pintype "passive"))
    )
    (net (code "6") (name "/Blue C6") (class "Default")
      (node (ref "LED14") (pin "3") (pinfunction "BLUE_CATHODE_3") (pintype "passive"))
      (node (ref "LED22") (pin "3") (pinfunction "BLUE_CATHODE_3") (pintype "passive"))
      (node (ref "LED30") (pin "3") (pinfunction "BLUE_CATHODE_3") (pintype "passive"))
      (node (ref "LED38") (pin "3") (pinfunction "BLUE_CATHODE_3") (pintype "passive"))
      (node (ref "LED46") (pin "3") (pinfunction "BLUE_CATHODE_3") (pintype "passive"))
      (node (ref "LED54") (pin "3") (pinfunction "BLUE_CATHODE_3") (pintype "passive"))
      (node (ref "LED6") (pin "3") (pinfunction "BLUE_CATHODE_3") (pintype "passive"))
      (node (ref "LED62") (pin "3") (pinfunction "BLUE_CATHODE_3") (pintype "passive"))
    )
    (net (code "7") (name "/Blue C7") (class "Default")
      (node (ref "LED23") (pin "3") (pinfunction "BLUE_CATHODE_3") (pintype "passive"))
      (node (ref "LED31") (pin "3") (pinfunction "BLUE_CATHODE_3") (pintype "passive"))
      (node (ref "LED39") (pin "3") (pinfunction "BLUE_CATHODE_3") (pintype "passive"))
      (node (ref "LED47") (pin "3") (pinfunction "BLUE_CATHODE_3") (pintype "passive"))
      (node (ref "LED55") (pin "3") (pinfunction "BLUE_CATHODE_3") (pintype "passive"))
      (node (ref "LED63") (pin "3") (pinfunction "BLUE_CATHODE_3") (pintype "passive"))
      (node (ref "LED7") (pin "3") (pinfunction "BLUE_CATHODE_3") (pintype "passive"))
      (node (ref "LED?15") (pin "3") (pinfunction "BLUE_CATHODE_3") (pintype "passive"))
    )
    (net (code "8") (name "/Blue C8") (class "Default")
      (node (ref "LED16") (pin "3") (pinfunction "BLUE_CATHODE_3") (pintype "passive"))
      (node (ref "LED24") (pin "3") (pinfunction "BLUE_CATHODE_3") (pintype "passive"))
      (node (ref "LED32") (pin "3") (pinfunction "BLUE_CATHODE_3") (pintype "passive"))
      (node (ref "LED40") (pin "3") (pinfunction "BLUE_CATHODE_3") (pintype "passive"))
      (node (ref "LED48") (pin "3") (pinfunction "BLUE_CATHODE_3") (pintype "passive"))
      (node (ref "LED56") (pin "3") (pinfunction "BLUE_CATHODE_3") (pintype "passive"))
      (node (ref "LED64") (pin "3") (pinfunction "BLUE_CATHODE_3") (pintype "passive"))
      (node (ref "LED8") (pin "3") (pinfunction "BLUE_CATHODE_3") (pintype "passive"))
    )
    (net (code "9") (name "/Column G1") (class "Default")
      (node (ref "R33") (pin "1") (pinfunction "1_1") (pintype "passive"))
    )
    (net (code "10") (name "/Column G2") (class "Default")
      (node (ref "R34") (pin "1") (pinfunction "1_1") (pintype "passive"))
    )
    (net (code "11") (name "/Column G3") (class "Default")
      (node (ref "R35") (pin "1") (pinfunction "1_1") (pintype "passive"))
    )
    (net (code "12") (name "/Column G4") (class "Default")
      (node (ref "R36") (pin "1") (pinfunction "1_1") (pintype "passive"))
    )
    (net (code "13") (name "/Column G5") (class "Default")
      (node (ref "R37") (pin "1") (pinfunction "1_1") (pintype "passive"))
    )
    (net (code "14") (name "/Column G6") (class "Default")
      (node (ref "R38") (pin "1") (pinfunction "1_1") (pintype "passive"))
    )
    (net (code "15") (name "/Column G7") (class "Default")
      (node (ref "R39") (pin "1") (pinfunction "1_1") (pintype "passive"))
    )
    (net (code "16") (name "/Column G8") (class "Default")
      (node (ref "R40") (pin "1") (pinfunction "1_1") (pintype "passive"))
    )
    (net (code "17") (name "/Column R1") (class "Default")
      (node (ref "R25") (pin "1") (pinfunction "1_1") (pintype "passive"))
    )
    (net (code "18") (name "/Column R2") (class "Default")
      (node (ref "R26") (pin "1") (pinfunction "1_1") (pintype "passive"))
    )
    (net (code "19") (name "/Column R3") (class "Default")
      (node (ref "R27") (pin "1") (pinfunction "1_1") (pintype "passive"))
    )
    (net (code "20") (name "/Column R4") (class "Default")
      (node (ref "R28") (pin "1") (pinfunction "1_1") (pintype "passive"))
    )
    (net (code "21") (name "/Column R5") (class "Default")
      (node (ref "R29") (pin "1") (pinfunction "1_1") (pintype "passive"))
    )
    (net (code "22") (name "/Column R6") (class "Default")
      (node (ref "R30") (pin "1") (pinfunction "1_1") (pintype "passive"))
    )
    (net (code "23") (name "/Column R7") (class "Default")
      (node (ref "R31") (pin "1") (pinfunction "1_1") (pintype "passive"))
    )
    (net (code "24") (name "/Column R8") (class "Default")
      (node (ref "R32") (pin "1") (pinfunction "1_1") (pintype "passive"))
    )
    (net (code "25") (name "/GND") (class "Default")
      (node (ref "U1") (pin "9") (pinfunction "GND_9") (pintype "power_in"))
      (node (ref "U2") (pin "9") (pinfunction "GND_9") (pintype "power_in"))
    )
    (net (code "26") (name "/Green C1") (class "Default")
      (node (ref "LED1") (pin "4") (pinfunction "GREEN_CATHODE_4") (pintype "passive"))
      (node (ref "LED17") (pin "4") (pinfunction "GREEN_CATHODE_4") (pintype "passive"))
      (node (ref "LED25") (pin "4") (pinfunction "GREEN_CATHODE_4") (pintype "passive"))
      (node (ref "LED33") (pin "4") (pinfunction "GREEN_CATHODE_4") (pintype "passive"))
      (node (ref "LED41") (pin "4") (pinfunction "GREEN_CATHODE_4") (pintype "passive"))
      (node (ref "LED49") (pin "4") (pinfunction "GREEN_CATHODE_4") (pintype "passive"))
      (node (ref "LED57") (pin "4") (pinfunction "GREEN_CATHODE_4") (pintype "passive"))
      (node (ref "LED9") (pin "4") (pinfunction "GREEN_CATHODE_4") (pintype "passive"))
      (node (ref "R9") (pin "2") (pinfunction "2_2") (pintype "passive"))
    )
    (net (code "27") (name "/Green C2") (class "Default")
      (node (ref "LED10") (pin "4") (pinfunction "GREEN_CATHODE_4") (pintype "passive"))
      (node (ref "LED18") (pin "4") (pinfunction "GREEN_CATHODE_4") (pintype "passive"))
      (node (ref "LED2") (pin "4") (pinfunction "GREEN_CATHODE_4") (pintype "passive"))
      (node (ref "LED26") (pin "4") (pinfunction "GREEN_CATHODE_4") (pintype "passive"))
      (node (ref "LED34") (pin "4") (pinfunction "GREEN_CATHODE_4") (pintype "passive"))
      (node (ref "LED42") (pin "4") (pinfunction "GREEN_CATHODE_4") (pintype "passive"))
      (node (ref "LED50") (pin "4") (pinfunction "GREEN_CATHODE_4") (pintype "passive"))
      (node (ref "LED58") (pin "4") (pinfunction "GREEN_CATHODE_4") (pintype "passive"))
      (node (ref "R10") (pin "2") (pinfunction "2_2") (pintype "passive"))
    )
    (net (code "28") (name "/Green C3") (class "Default")
      (node (ref "LED11") (pin "4") (pinfunction "GREEN_CATHODE_4") (pintype "passive"))
      (node (ref "LED19") (pin "4") (pinfunction "GREEN_CATHODE_4") (pintype "passive"))
      (node (ref "LED27") (pin "4") (pinfunction "GREEN_CATHODE_4") (pintype "passive"))
      (node (ref "LED3") (pin "4") (pinfunction "GREEN_CATHODE_4") (pintype "passive"))
      (node (ref "LED35") (pin "4") (pinfunction "GREEN_CATHODE_4") (pintype "passive"))
      (node (ref "LED43") (pin "4") (pinfunction "GREEN_CATHODE_4") (pintype "passive"))
      (node (ref "LED51") (pin "4") (pinfunction "GREEN_CATHODE_4") (pintype "passive"))
      (node (ref "LED59") (pin "4") (pinfunction "GREEN_CATHODE_4") (pintype "passive"))
      (node (ref "R11") (pin "2") (pinfunction "2_2") (pintype "passive"))
    )
    (net (code "29") (name "/Green C4") (class "Default")
      (node (ref "LED12") (pin "4") (pinfunction "GREEN_CATHODE_4") (pintype "passive"))
      (node (ref "LED20") (pin "4") (pinfunction "GREEN_CATHODE_4") (pintype "passive"))
      (node (ref "LED28") (pin "4") (pinfunction "GREEN_CATHODE_4") (pintype "passive"))
      (node (ref "LED36") (pin "4") (pinfunction "GREEN_CATHODE_4") (pintype "passive"))
      (node (ref "LED4") (pin "4") (pinfunction "GREEN_CATHODE_4") (pintype "passive"))
      (node (ref "LED44") (pin "4") (pinfunction "GREEN_CATHODE_4") (pintype "passive"))
      (node (ref "LED52") (pin "4") (pinfunction "GREEN_CATHODE_4") (pintype "passive"))
      (node (ref "LED60") (pin "4") (pinfunction "GREEN_CATHODE_4") (pintype "passive"))
      (node (ref "R12") (pin "2") (pinfunction "2_2") (pintype "passive"))
    )
    (net (code "30") (name "/Green C5") (class "Default")
      (node (ref "LED13") (pin "4") (pinfunction "GREEN_CATHODE_4") (pintype "passive"))
      (node (ref "LED21") (pin "4") (pinfunction "GREEN_CATHODE_4") (pintype "passive"))
      (node (ref "LED29") (pin "4") (pinfunction "GREEN_CATHODE_4") (pintype "passive"))
      (node (ref "LED37") (pin "4") (pinfunction "GREEN_CATHODE_4") (pintype "passive"))
      (node (ref "LED45") (pin "4") (pinfunction "GREEN_CATHODE_4") (pintype "passive"))
      (node (ref "LED5") (pin "4") (pinfunction "GREEN_CATHODE_4") (pintype "passive"))
      (node (ref "LED53") (pin "4") (pinfunction "GREEN_CATHODE_4") (pintype "passive"))
      (node (ref "LED61") (pin "4") (pinfunction "GREEN_CATHODE_4") (pintype "passive"))
      (node (ref "R13") (pin "2") (pinfunction "2_2") (pintype "passive"))
    )
    (net (code "31") (name "/Green C6") (class "Default")
      (node (ref "LED14") (pin "4") (pinfunction "GREEN_CATHODE_4") (pintype "passive"))
      (node (ref "LED22") (pin "4") (pinfunction "GREEN_CATHODE_4") (pintype "passive"))
      (node (ref "LED30") (pin "4") (pinfunction "GREEN_CATHODE_4") (pintype "passive"))
      (node (ref "LED38") (pin "4") (pinfunction "GREEN_CATHODE_4") (pintype "passive"))
      (node (ref "LED46") (pin "4") (pinfunction "GREEN_CATHODE_4") (pintype "passive"))
      (node (ref "LED54") (pin "4") (pinfunction "GREEN_CATHODE_4") (pintype "passive"))
      (node (ref "LED6") (pin "4") (pinfunction "GREEN_CATHODE_4") (pintype "passive"))
      (node (ref "LED62") (pin "4") (pinfunction "GREEN_CATHODE_4") (pintype "passive"))
      (node (ref "R14") (pin "2") (pinfunction "2_2") (pintype "passive"))
    )
    (net (code "32") (name "/Green C7") (class "Default")
      (node (ref "LED23") (pin "4") (pinfunction "GREEN_CATHODE_4") (pintype "passive"))
      (node (ref "LED31") (pin "4") (pinfunction "GREEN_CATHODE_4") (pintype "passive"))
      (node (ref "LED39") (pin "4") (pinfunction "GREEN_CATHODE_4") (pintype "passive"))
      (node (ref "LED47") (pin "4") (pinfunction "GREEN_CATHODE_4") (pintype "passive"))
      (node (ref "LED55") (pin "4") (pinfunction "GREEN_CATHODE_4") (pintype "passive"))
      (node (ref "LED63") (pin "4") (pinfunction "GREEN_CATHODE_4") (pintype "passive"))
      (node (ref "LED7") (pin "4") (pinfunction "GREEN_CATHODE_4") (pintype "passive"))
      (node (ref "LED?15") (pin "4") (pinfunction "GREEN_CATHODE_4") (pintype "passive"))
      (node (ref "R15") (pin "2") (pinfunction "2_2") (pintype "passive"))
    )
    (net (code "33") (name "/Green C8") (class "Default")
      (node (ref "LED16") (pin "4") (pinfunction "GREEN_CATHODE_4") (pintype "passive"))
      (node (ref "LED24") (pin "4") (pinfunction "GREEN_CATHODE_4") (pintype "passive"))
      (node (ref "LED32") (pin "4") (pinfunction "GREEN_CATHODE_4") (pintype "passive"))
      (node (ref "LED40") (pin "4") (pinfunction "GREEN_CATHODE_4") (pintype "passive"))
      (node (ref "LED48") (pin "4") (pinfunction "GREEN_CATHODE_4") (pintype "passive"))
      (node (ref "LED56") (pin "4") (pinfunction "GREEN_CATHODE_4") (pintype "passive"))
      (node (ref "LED64") (pin "4") (pinfunction "GREEN_CATHODE_4") (pintype "passive"))
      (node (ref "LED8") (pin "4") (pinfunction "GREEN_CATHODE_4") (pintype "passive"))
    )
    (net (code "34") (name "/Power") (class "Default")
      (node (ref "Q1") (pin "1") (pinfunction "E_1") (pintype "passive"))
      (node (ref "Q2") (pin "1") (pinfunction "E_1") (pintype "passive"))
      (node (ref "Q3") (pin "1") (pinfunction "E_1") (pintype "passive"))
      (node (ref "Q4") (pin "1") (pinfunction "E_1") (pintype "passive"))
      (node (ref "Q5") (pin "1") (pinfunction "E_1") (pintype "passive"))
      (node (ref "Q6") (pin "1") (pinfunction "E_1") (pintype "passive"))
      (node (ref "Q7") (pin "1") (pinfunction "E_1") (pintype "passive"))
      (node (ref "Q8") (pin "1") (pinfunction "E_1") (pintype "passive"))
    )
    (net (code "35") (name "/Red C1") (class "Default")
      (node (ref "LED1") (pin "1") (pinfunction "RED_CATHODE_1") (pintype "passive"))
      (node (ref "LED17") (pin "1") (pinfunction "RED_CATHODE_1") (pintype "passive"))
      (node (ref "LED25") (pin "1") (pinfunction "RED_CATHODE_1") (pintype "passive"))
      (node (ref "LED33") (pin "1") (pinfunction "RED_CATHODE_1") (pintype "passive"))
      (node (ref "LED41") (pin "1") (pinfunction "RED_CATHODE_1") (pintype "passive"))
      (node (ref "LED49") (pin "1") (pinfunction "RED_CATHODE_1") (pintype "passive"))
      (node (ref "LED57") (pin "1") (pinfunction "RED_CATHODE_1") (pintype "passive"))
      (node (ref "LED9") (pin "1") (pinfunction "RED_CATHODE_1") (pintype "passive"))
      (node (ref "R17") (pin "2") (pinfunction "2_2") (pintype "passive"))
    )
    (net (code "36") (name "/Red C2") (class "Default")
      (node (ref "LED10") (pin "1") (pinfunction "RED_CATHODE_1") (pintype "passive"))
      (node (ref "LED18") (pin "1") (pinfunction "RED_CATHODE_1") (pintype "passive"))
      (node (ref "LED2") (pin "1") (pinfunction "RED_CATHODE_1") (pintype "passive"))
      (node (ref "LED26") (pin "1") (pinfunction "RED_CATHODE_1") (pintype "passive"))
      (node (ref "LED34") (pin "1") (pinfunction "RED_CATHODE_1") (pintype "passive"))
      (node (ref "LED42") (pin "1") (pinfunction "RED_CATHODE_1") (pintype "passive"))
      (node (ref "LED50") (pin "1") (pinfunction "RED_CATHODE_1") (pintype "passive"))
      (node (ref "LED58") (pin "1") (pinfunction "RED_CATHODE_1") (pintype "passive"))
      (node (ref "R18") (pin "2") (pinfunction "2_2") (pintype "passive"))
    )
    (net (code "37") (name "/Red C3") (class "Default")
      (node (ref "LED11") (pin "1") (pinfunction "RED_CATHODE_1") (pintype "passive"))
      (node (ref "LED19") (pin "1") (pinfunction "RED_CATHODE_1") (pintype "passive"))
      (node (ref "LED27") (pin "1") (pinfunction "RED_CATHODE_1") (pintype "passive"))
      (node (ref "LED3") (pin "1") (pinfunction "RED_CATHODE_1") (pintype "passive"))
      (node (ref "LED35") (pin "1") (pinfunction "RED_CATHODE_1") (pintype "passive"))
      (node (ref "LED43") (pin "1") (pinfunction "RED_CATHODE_1") (pintype "passive"))
      (node (ref "LED51") (pin "1") (pinfunction "RED_CATHODE_1") (pintype "passive"))
      (node (ref "LED59") (pin "1") (pinfunction "RED_CATHODE_1") (pintype "passive"))
      (node (ref "R19") (pin "2") (pinfunction "2_2") (pintype "passive"))
    )
    (net (code "38") (name "/Red C4") (class "Default")
      (node (ref "LED12") (pin "1") (pinfunction "RED_CATHODE_1") (pintype "passive"))
      (node (ref "LED20") (pin "1") (pinfunction "RED_CATHODE_1") (pintype "passive"))
      (node (ref "LED28") (pin "1") (pinfunction "RED_CATHODE_1") (pintype "passive"))
      (node (ref "LED36") (pin "1") (pinfunction "RED_CATHODE_1") (pintype "passive"))
      (node (ref "LED4") (pin "1") (pinfunction "RED_CATHODE_1") (pintype "passive"))
      (node (ref "LED44") (pin "1") (pinfunction "RED_CATHODE_1") (pintype "passive"))
      (node (ref "LED52") (pin "1") (pinfunction "RED_CATHODE_1") (pintype "passive"))
      (node (ref "LED60") (pin "1") (pinfunction "RED_CATHODE_1") (pintype "passive"))
      (node (ref "R20") (pin "2") (pinfunction "2_2") (pintype "passive"))
    )
    (net (code "39") (name "/Red C5") (class "Default")
      (node (ref "LED13") (pin "1") (pinfunction "RED_CATHODE_1") (pintype "passive"))
      (node (ref "LED21") (pin "1") (pinfunction "RED_CATHODE_1") (pintype "passive"))
      (node (ref "LED29") (pin "1") (pinfunction "RED_CATHODE_1") (pintype "passive"))
      (node (ref "LED37") (pin "1") (pinfunction "RED_CATHODE_1") (pintype "passive"))
      (node (ref "LED45") (pin "1") (pinfunction "RED_CATHODE_1") (pintype "passive"))
      (node (ref "LED5") (pin "1") (pinfunction "RED_CATHODE_1") (pintype "passive"))
      (node (ref "LED53") (pin "1") (pinfunction "RED_CATHODE_1") (pintype "passive"))
      (node (ref "LED61") (pin "1") (pinfunction "RED_CATHODE_1") (pintype "passive"))
      (node (ref "R21") (pin "2") (pinfunction "2_2") (pintype "passive"))
    )
    (net (code "40") (name "/Red C6") (class "Default")
      (node (ref "LED14") (pin "1") (pinfunction "RED_CATHODE_1") (pintype "passive"))
      (node (ref "LED22") (pin "1") (pinfunction "RED_CATHODE_1") (pintype "passive"))
      (node (ref "LED30") (pin "1") (pinfunction "RED_CATHODE_1") (pintype "passive"))
      (node (ref "LED38") (pin "1") (pinfunction "RED_CATHODE_1") (pintype "passive"))
      (node (ref "LED46") (pin "1") (pinfunction "RED_CATHODE_1") (pintype "passive"))
      (node (ref "LED54") (pin "1") (pinfunction "RED_CATHODE_1") (pintype "passive"))
      (node (ref "LED6") (pin "1") (pinfunction "RED_CATHODE_1") (pintype "passive"))
      (node (ref "LED62") (pin "1") (pinfunction "RED_CATHODE_1") (pintype "passive"))
      (node (ref "R22") (pin "2") (pinfunction "2_2") (pintype "passive"))
    )
    (net (code "41") (name "/Red C7") (class "Default")
      (node (ref "LED23") (pin "1") (pinfunction "RED_CATHODE_1") (pintype "passive"))
      (node (ref "LED31") (pin "1") (pinfunction "RED_CATHODE_1") (pintype "passive"))
      (node (ref "LED39") (pin "1") (pinfunction "RED_CATHODE_1") (pintype "passive"))
      (node (ref "LED47") (pin "1") (pinfunction "RED_CATHODE_1") (pintype "passive"))
      (node (ref "LED55") (pin "1") (pinfunction "RED_CATHODE_1") (pintype "passive"))
      (node (ref "LED63") (pin "1") (pinfunction "RED_CATHODE_1") (pintype "passive"))
      (node (ref "LED7") (pin "1") (pinfunction "RED_CATHODE_1") (pintype "passive"))
      (node (ref "LED?15") (pin "1") (pinfunction "RED_CATHODE_1") (pintype "passive"))
      (node (ref "R23") (pin "2") (pinfunction "2_2") (pintype "passive"))
    )
    (net (code "42") (name "/Red C8") (class "Default")
      (node (ref "LED16") (pin "1") (pinfunction "RED_CATHODE_1") (pintype "passive"))
      (node (ref "LED24") (pin "1") (pinfunction "RED_CATHODE_1") (pintype "passive"))
      (node (ref "LED32") (pin "1") (pinfunction "RED_CATHODE_1") (pintype "passive"))
      (node (ref "LED40") (pin "1") (pinfunction "RED_CATHODE_1") (pintype "passive"))
      (node (ref "LED48") (pin "1") (pinfunction "RED_CATHODE_1") (pintype "passive"))
      (node (ref "LED56") (pin "1") (pinfunction "RED_CATHODE_1") (pintype "passive"))
      (node (ref "LED64") (pin "1") (pinfunction "RED_CATHODE_1") (pintype "passive"))
      (node (ref "LED8") (pin "1") (pinfunction "RED_CATHODE_1") (pintype "passive"))
      (node (ref "R24") (pin "2") (pinfunction "2_2") (pintype "passive"))
    )
    (net (code "43") (name "/Row1") (class "Default")
      (node (ref "R1") (pin "1") (pinfunction "1_1") (pintype "passive"))
    )
    (net (code "44") (name "/Row2") (class "Default")
      (node (ref "R2") (pin "1") (pinfunction "1_1") (pintype "passive"))
    )
    (net (code "45") (name "/Row3") (class "Default")
      (node (ref "R3") (pin "1") (pinfunction "1_1") (pintype "passive"))
    )
    (net (code "46") (name "/Row4") (class "Default")
      (node (ref "R4") (pin "1") (pinfunction "1_1") (pintype "passive"))
    )
    (net (code "47") (name "/Row5") (class "Default")
      (node (ref "R5") (pin "1") (pinfunction "1_1") (pintype "passive"))
    )
    (net (code "48") (name "/Row6") (class "Default")
      (node (ref "R6") (pin "1") (pinfunction "1_1") (pintype "passive"))
    )
    (net (code "49") (name "/Row7") (class "Default")
      (node (ref "R7") (pin "1") (pinfunction "1_1") (pintype "passive"))
    )
    (net (code "50") (name "/Row8") (class "Default")
      (node (ref "R8") (pin "1") (pinfunction "1_1") (pintype "passive"))
    )
    (net (code "51") (name "Net-(LED1-COMMON_ANODE)") (class "Default")
      (node (ref "LED1") (pin "2") (pinfunction "COMMON_ANODE_2") (pintype "passive"))
      (node (ref "LED17") (pin "2") (pinfunction "COMMON_ANODE_2") (pintype "passive"))
      (node (ref "LED25") (pin "2") (pinfunction "COMMON_ANODE_2") (pintype "passive"))
      (node (ref "LED33") (pin "2") (pinfunction "COMMON_ANODE_2") (pintype "passive"))
      (node (ref "LED41") (pin "2") (pinfunction "COMMON_ANODE_2") (pintype "passive"))
      (node (ref "LED49") (pin "2") (pinfunction "COMMON_ANODE_2") (pintype "passive"))
      (node (ref "LED57") (pin "2") (pinfunction "COMMON_ANODE_2") (pintype "passive"))
      (node (ref "LED9") (pin "2") (pinfunction "COMMON_ANODE_2") (pintype "passive"))
      (node (ref "Q1") (pin "3") (pinfunction "C_3") (pintype "passive"))
    )
    (net (code "52") (name "Net-(LED10-COMMON_ANODE)") (class "Default")
      (node (ref "LED10") (pin "2") (pinfunction "COMMON_ANODE_2") (pintype "passive"))
      (node (ref "LED18") (pin "2") (pinfunction "COMMON_ANODE_2") (pintype "passive"))
      (node (ref "LED2") (pin "2") (pinfunction "COMMON_ANODE_2") (pintype "passive"))
      (node (ref "LED26") (pin "2") (pinfunction "COMMON_ANODE_2") (pintype "passive"))
      (node (ref "LED34") (pin "2") (pinfunction "COMMON_ANODE_2") (pintype "passive"))
      (node (ref "LED42") (pin "2") (pinfunction "COMMON_ANODE_2") (pintype "passive"))
      (node (ref "LED50") (pin "2") (pinfunction "COMMON_ANODE_2") (pintype "passive"))
      (node (ref "LED58") (pin "2") (pinfunction "COMMON_ANODE_2") (pintype "passive"))
      (node (ref "Q2") (pin "3") (pinfunction "C_3") (pintype "passive"))
    )
    (net (code "53") (name "Net-(LED11-COMMON_ANODE)") (class "Default")
      (node (ref "LED11") (pin "2") (pinfunction "COMMON_ANODE_2") (pintype "passive"))
      (node (ref "LED19") (pin "2") (pinfunction "COMMON_ANODE_2") (pintype "passive"))
      (node (ref "LED27") (pin "2") (pinfunction "COMMON_ANODE_2") (pintype "passive"))
      (node (ref "LED3") (pin "2") (pinfunction "COMMON_ANODE_2") (pintype "passive"))
      (node (ref "LED35") (pin "2") (pinfunction "COMMON_ANODE_2") (pintype "passive"))
      (node (ref "LED43") (pin "2") (pinfunction "COMMON_ANODE_2") (pintype "passive"))
      (node (ref "LED51") (pin "2") (pinfunction "COMMON_ANODE_2") (pintype "passive"))
      (node (ref "LED59") (pin "2") (pinfunction "COMMON_ANODE_2") (pintype "passive"))
      (node (ref "Q3") (pin "3") (pinfunction "C_3") (pintype "passive"))
    )
    (net (code "54") (name "Net-(LED12-COMMON_ANODE)") (class "Default")
      (node (ref "LED12") (pin "2") (pinfunction "COMMON_ANODE_2") (pintype "passive"))
      (node (ref "LED20") (pin "2") (pinfunction "COMMON_ANODE_2") (pintype "passive"))
      (node (ref "LED28") (pin "2") (pinfunction "COMMON_ANODE_2") (pintype "passive"))
      (node (ref "LED36") (pin "2") (pinfunction "COMMON_ANODE_2") (pintype "passive"))
      (node (ref "LED4") (pin "2") (pinfunction "COMMON_ANODE_2") (pintype "passive"))
      (node (ref "LED44") (pin "2") (pinfunction "COMMON_ANODE_2") (pintype "passive"))
      (node (ref "LED52") (pin "2") (pinfunction "COMMON_ANODE_2") (pintype "passive"))
      (node (ref "LED60") (pin "2") (pinfunction "COMMON_ANODE_2") (pintype "passive"))
      (node (ref "Q4") (pin "3") (pinfunction "C_3") (pintype "passive"))
    )
    (net (code "55") (name "Net-(LED13-COMMON_ANODE)") (class "Default")
      (node (ref "LED13") (pin "2") (pinfunction "COMMON_ANODE_2") (pintype "passive"))
      (node (ref "LED21") (pin "2") (pinfunction "COMMON_ANODE_2") (pintype "passive"))
      (node (ref "LED29") (pin "2") (pinfunction "COMMON_ANODE_2") (pintype "passive"))
      (node (ref "LED37") (pin "2") (pinfunction "COMMON_ANODE_2") (pintype "passive"))
      (node (ref "LED45") (pin "2") (pinfunction "COMMON_ANODE_2") (pintype "passive"))
      (node (ref "LED5") (pin "2") (pinfunction "COMMON_ANODE_2") (pintype "passive"))
      (node (ref "LED53") (pin "2") (pinfunction "COMMON_ANODE_2") (pintype "passive"))
      (node (ref "LED61") (pin "2") (pinfunction "COMMON_ANODE_2") (pintype "passive"))
      (node (ref "Q5") (pin "3") (pinfunction "C_3") (pintype "passive"))
    )
    (net (code "56") (name "Net-(LED14-COMMON_ANODE)") (class "Default")
      (node (ref "LED14") (pin "2") (pinfunction "COMMON_ANODE_2") (pintype "passive"))
      (node (ref "LED22") (pin "2") (pinfunction "COMMON_ANODE_2") (pintype "passive"))
      (node (ref "LED30") (pin "2") (pinfunction "COMMON_ANODE_2") (pintype "passive"))
      (node (ref "LED38") (pin "2") (pinfunction "COMMON_ANODE_2") (pintype "passive"))
      (node (ref "LED46") (pin "2") (pinfunction "COMMON_ANODE_2") (pintype "passive"))
      (node (ref "LED54") (pin "2") (pinfunction "COMMON_ANODE_2") (pintype "passive"))
      (node (ref "LED6") (pin "2") (pinfunction "COMMON_ANODE_2") (pintype "passive"))
      (node (ref "LED62") (pin "2") (pinfunction "COMMON_ANODE_2") (pintype "passive"))
      (node (ref "Q6") (pin "3") (pinfunction "C_3") (pintype "passive"))
    )
    (net (code "57") (name "Net-(LED16-COMMON_ANODE)") (class "Default")
      (node (ref "LED16") (pin "2") (pinfunction "COMMON_ANODE_2") (pintype "passive"))
      (node (ref "LED24") (pin "2") (pinfunction "COMMON_ANODE_2") (pintype "passive"))
      (node (ref "LED32") (pin "2") (pinfunction "COMMON_ANODE_2") (pintype "passive"))
      (node (ref "LED40") (pin "2") (pinfunction "COMMON_ANODE_2") (pintype "passive"))
      (node (ref "LED48") (pin "2") (pinfunction "COMMON_ANODE_2") (pintype "passive"))
      (node (ref "LED56") (pin "2") (pinfunction "COMMON_ANODE_2") (pintype "passive"))
      (node (ref "LED64") (pin "2") (pinfunction "COMMON_ANODE_2") (pintype "passive"))
      (node (ref "LED8") (pin "2") (pinfunction "COMMON_ANODE_2") (pintype "passive"))
      (node (ref "Q8") (pin "3") (pinfunction "C_3") (pintype "passive"))
    )
    (net (code "58") (name "Net-(LED23-COMMON_ANODE)") (class "Default")
      (node (ref "LED23") (pin "2") (pinfunction "COMMON_ANODE_2") (pintype "passive"))
      (node (ref "LED31") (pin "2") (pinfunction "COMMON_ANODE_2") (pintype "passive"))
      (node (ref "LED39") (pin "2") (pinfunction "COMMON_ANODE_2") (pintype "passive"))
      (node (ref "LED47") (pin "2") (pinfunction "COMMON_ANODE_2") (pintype "passive"))
      (node (ref "LED55") (pin "2") (pinfunction "COMMON_ANODE_2") (pintype "passive"))
      (node (ref "LED63") (pin "2") (pinfunction "COMMON_ANODE_2") (pintype "passive"))
      (node (ref "LED7") (pin "2") (pinfunction "COMMON_ANODE_2") (pintype "passive"))
      (node (ref "LED?15") (pin "2") (pinfunction "COMMON_ANODE_2") (pintype "passive"))
      (node (ref "Q7") (pin "3") (pinfunction "C_3") (pintype "passive"))
    )
    (net (code "59") (name "Net-(Q1-B)") (class "Default")
      (node (ref "Q1") (pin "2") (pinfunction "B_2") (pintype "passive"))
      (node (ref "R1") (pin "2") (pinfunction "2_2") (pintype "passive"))
    )
    (net (code "60") (name "Net-(Q2-B)") (class "Default")
      (node (ref "Q2") (pin "2") (pinfunction "B_2") (pintype "passive"))
      (node (ref "R2") (pin "2") (pinfunction "2_2") (pintype "passive"))
    )
    (net (code "61") (name "Net-(Q3-B)") (class "Default")
      (node (ref "Q3") (pin "2") (pinfunction "B_2") (pintype "passive"))
      (node (ref "R3") (pin "2") (pinfunction "2_2") (pintype "passive"))
    )
    (net (code "62") (name "Net-(Q4-B)") (class "Default")
      (node (ref "Q4") (pin "2") (pinfunction "B_2") (pintype "passive"))
      (node (ref "R4") (pin "2") (pinfunction "2_2") (pintype "passive"))
    )
    (net (code "63") (name "Net-(Q5-B)") (class "Default")
      (node (ref "Q5") (pin "2") (pinfunction "B_2") (pintype "passive"))
      (node (ref "R5") (pin "2") (pinfunction "2_2") (pintype "passive"))
    )
    (net (code "64") (name "Net-(Q6-B)") (class "Default")
      (node (ref "Q6") (pin "2") (pinfunction "B_2") (pintype "passive"))
      (node (ref "R6") (pin "2") (pinfunction "2_2") (pintype "passive"))
    )
    (net (code "65") (name "Net-(Q7-B)") (class "Default")
      (node (ref "Q7") (pin "2") (pinfunction "B_2") (pintype "passive"))
      (node (ref "R7") (pin "2") (pinfunction "2_2") (pintype "passive"))
    )
    (net (code "66") (name "Net-(Q8-B)") (class "Default")
      (node (ref "Q8") (pin "2") (pinfunction "B_2") (pintype "passive"))
      (node (ref "R8") (pin "2") (pinfunction "2_2") (pintype "passive"))
    )
    (net (code "67") (name "Net-(U1-IN_1)") (class "Default")
      (node (ref "R33") (pin "2") (pinfunction "2_2") (pintype "passive"))
      (node (ref "U1") (pin "1") (pinfunction "IN_1_1") (pintype "input"))
    )
    (net (code "68") (name "Net-(U1-IN_2)") (class "Default")
      (node (ref "R34") (pin "2") (pinfunction "2_2") (pintype "passive"))
      (node (ref "U1") (pin "2") (pinfunction "IN_2_2") (pintype "input"))
    )
    (net (code "69") (name "Net-(U1-IN_3)") (class "Default")
      (node (ref "R35") (pin "2") (pinfunction "2_2") (pintype "passive"))
      (node (ref "U1") (pin "3") (pinfunction "IN_3_3") (pintype "input"))
    )
    (net (code "70") (name "Net-(U1-IN_4)") (class "Default")
      (node (ref "R36") (pin "2") (pinfunction "2_2") (pintype "passive"))
      (node (ref "U1") (pin "4") (pinfunction "IN_4_4") (pintype "input"))
    )
    (net (code "71") (name "Net-(U1-IN_5)") (class "Default")
      (node (ref "R37") (pin "2") (pinfunction "2_2") (pintype "passive"))
      (node (ref "U1") (pin "5") (pinfunction "IN_5_5") (pintype "input"))
    )
    (net (code "72") (name "Net-(U1-IN_6)") (class "Default")
      (node (ref "R38") (pin "2") (pinfunction "2_2") (pintype "passive"))
      (node (ref "U1") (pin "6") (pinfunction "IN_6_6") (pintype "input"))
    )
    (net (code "73") (name "Net-(U1-IN_7)") (class "Default")
      (node (ref "R39") (pin "2") (pinfunction "2_2") (pintype "passive"))
      (node (ref "U1") (pin "7") (pinfunction "IN_7_7") (pintype "input"))
    )
    (net (code "74") (name "Net-(U1-IN_8)") (class "Default")
      (node (ref "R40") (pin "2") (pinfunction "2_2") (pintype "passive"))
      (node (ref "U1") (pin "8") (pinfunction "IN_8_8") (pintype "input"))
    )
    (net (code "75") (name "Net-(U1-OUT_1)") (class "Default")
      (node (ref "R9") (pin "1") (pinfunction "1_1") (pintype "passive"))
      (node (ref "U1") (pin "18") (pinfunction "OUT_1_18") (pintype "output"))
    )
    (net (code "76") (name "Net-(U1-OUT_2)") (class "Default")
      (node (ref "R10") (pin "1") (pinfunction "1_1") (pintype "passive"))
      (node (ref "U1") (pin "17") (pinfunction "OUT_2_17") (pintype "output"))
    )
    (net (code "77") (name "Net-(U1-OUT_3)") (class "Default")
      (node (ref "R11") (pin "1") (pinfunction "1_1") (pintype "passive"))
      (node (ref "U1") (pin "16") (pinfunction "OUT_3_16") (pintype "output"))
    )
    (net (code "78") (name "Net-(U1-OUT_4)") (class "Default")
      (node (ref "R12") (pin "1") (pinfunction "1_1") (pintype "passive"))
      (node (ref "U1") (pin "15") (pinfunction "OUT_4_15") (pintype "output"))
    )
    (net (code "79") (name "Net-(U1-OUT_5)") (class "Default")
      (node (ref "R13") (pin "1") (pinfunction "1_1") (pintype "passive"))
      (node (ref "U1") (pin "14") (pinfunction "OUT_5_14") (pintype "output"))
    )
    (net (code "80") (name "Net-(U1-OUT_6)") (class "Default")
      (node (ref "R14") (pin "1") (pinfunction "1_1") (pintype "passive"))
      (node (ref "U1") (pin "13") (pinfunction "OUT_6_13") (pintype "output"))
    )
    (net (code "81") (name "Net-(U1-OUT_7)") (class "Default")
      (node (ref "R15") (pin "1") (pinfunction "1_1") (pintype "passive"))
      (node (ref "U1") (pin "12") (pinfunction "OUT_7_12") (pintype "output"))
    )
    (net (code "82") (name "Net-(U1-OUT_8)") (class "Default")
      (node (ref "R16") (pin "1") (pinfunction "1_1") (pintype "passive"))
      (node (ref "U1") (pin "11") (pinfunction "OUT_8_11") (pintype "output"))
    )
    (net (code "83") (name "Net-(U2-IN_1)") (class "Default")
      (node (ref "R25") (pin "2") (pinfunction "2_2") (pintype "passive"))
      (node (ref "U2") (pin "1") (pinfunction "IN_1_1") (pintype "input"))
    )
    (net (code "84") (name "Net-(U2-IN_2)") (class "Default")
      (node (ref "R26") (pin "2") (pinfunction "2_2") (pintype "passive"))
      (node (ref "U2") (pin "2") (pinfunction "IN_2_2") (pintype "input"))
    )
    (net (code "85") (name "Net-(U2-IN_3)") (class "Default")
      (node (ref "R27") (pin "2") (pinfunction "2_2") (pintype "passive"))
      (node (ref "U2") (pin "3") (pinfunction "IN_3_3") (pintype "input"))
    )
    (net (code "86") (name "Net-(U2-IN_4)") (class "Default")
      (node (ref "R28") (pin "2") (pinfunction "2_2") (pintype "passive"))
      (node (ref "U2") (pin "4") (pinfunction "IN_4_4") (pintype "input"))
    )
    (net (code "87") (name "Net-(U2-IN_5)") (class "Default")
      (node (ref "R29") (pin "2") (pinfunction "2_2") (pintype "passive"))
      (node (ref "U2") (pin "5") (pinfunction "IN_5_5") (pintype "input"))
    )
    (net (code "88") (name "Net-(U2-IN_6)") (class "Default")
      (node (ref "R30") (pin "2") (pinfunction "2_2") (pintype "passive"))
      (node (ref "U2") (pin "6") (pinfunction "IN_6_6") (pintype "input"))
    )
    (net (code "89") (name "Net-(U2-IN_7)") (class "Default")
      (node (ref "R31") (pin "2") (pinfunction "2_2") (pintype "passive"))
      (node (ref "U2") (pin "7") (pinfunction "IN_7_7") (pintype "input"))
    )
    (net (code "90") (name "Net-(U2-IN_8)") (class "Default")
      (node (ref "R32") (pin "2") (pinfunction "2_2") (pintype "passive"))
      (node (ref "U2") (pin "8") (pinfunction "IN_8_8") (pintype "input"))
    )
    (net (code "91") (name "Net-(U2-OUT_1)") (class "Default")
      (node (ref "R17") (pin "1") (pinfunction "1_1") (pintype "passive"))
      (node (ref "U2") (pin "18") (pinfunction "OUT_1_18") (pintype "output"))
    )
    (net (code "92") (name "Net-(U2-OUT_2)") (class "Default")
      (node (ref "R18") (pin "1") (pinfunction "1_1") (pintype "passive"))
      (node (ref "U2") (pin "17") (pinfunction "OUT_2_17") (pintype "output"))
    )
    (net (code "93") (name "Net-(U2-OUT_3)") (class "Default")
      (node (ref "R19") (pin "1") (pinfunction "1_1") (pintype "passive"))
      (node (ref "U2") (pin "16") (pinfunction "OUT_3_16") (pintype "output"))
    )
    (net (code "94") (name "Net-(U2-OUT_4)") (class "Default")
      (node (ref "R20") (pin "1") (pinfunction "1_1") (pintype "passive"))
      (node (ref "U2") (pin "15") (pinfunction "OUT_4_15") (pintype "output"))
    )
    (net (code "95") (name "Net-(U2-OUT_5)") (class "Default")
      (node (ref "R21") (pin "1") (pinfunction "1_1") (pintype "passive"))
      (node (ref "U2") (pin "14") (pinfunction "OUT_5_14") (pintype "output"))
    )
    (net (code "96") (name "Net-(U2-OUT_6)") (class "Default")
      (node (ref "R22") (pin "1") (pinfunction "1_1") (pintype "passive"))
      (node (ref "U2") (pin "13") (pinfunction "OUT_6_13") (pintype "output"))
    )
    (net (code "97") (name "Net-(U2-OUT_7)") (class "Default")
      (node (ref "R23") (pin "1") (pinfunction "1_1") (pintype "passive"))
      (node (ref "U2") (pin "12") (pinfunction "OUT_7_12") (pintype "output"))
    )
    (net (code "98") (name "Net-(U2-OUT_8)") (class "Default")
      (node (ref "R24") (pin "1") (pinfunction "1_1") (pintype "passive"))
      (node (ref "U2") (pin "11") (pinfunction "OUT_8_11") (pintype "output"))
    )
    (net (code "99") (name "unconnected-(R16-Pad2)") (class "Default")
      (node (ref "R16") (pin "2") (pinfunction "2_2") (pintype "passive"))
    )
    (net (code "100") (name "unconnected-(U1-COMMON-Pad10)") (class "Default")
      (node (ref "U1") (pin "10") (pinfunction "COMMON_10") (pintype "output"))
    )
    (net (code "101") (name "unconnected-(U2-COMMON-Pad10)") (class "Default")
      (node (ref "U2") (pin "10") (pinfunction "COMMON_10") (pintype "output"))
    )
  )
)
